# design.net
KiCad netlist of a schematic drawn in Altium Designer
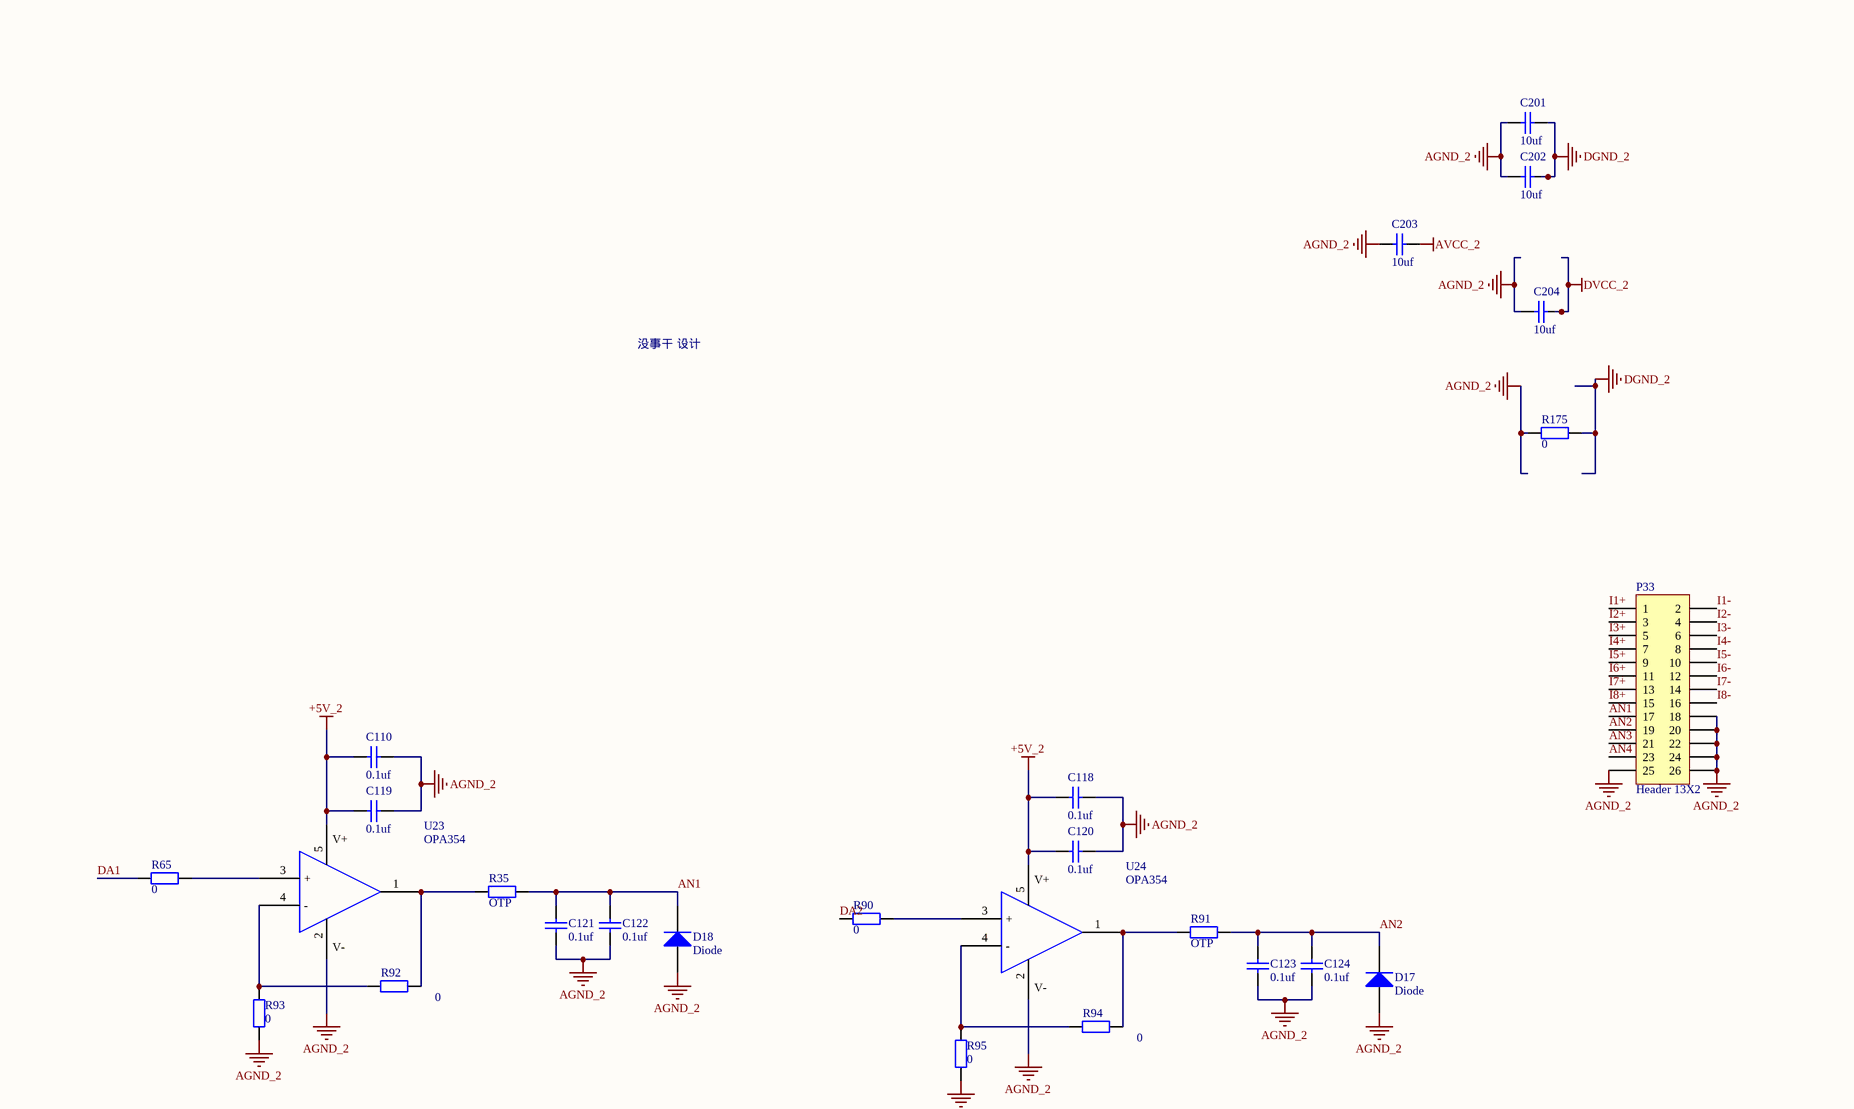
[diagram p0: 模拟量输入输出.SchDoc, top left]
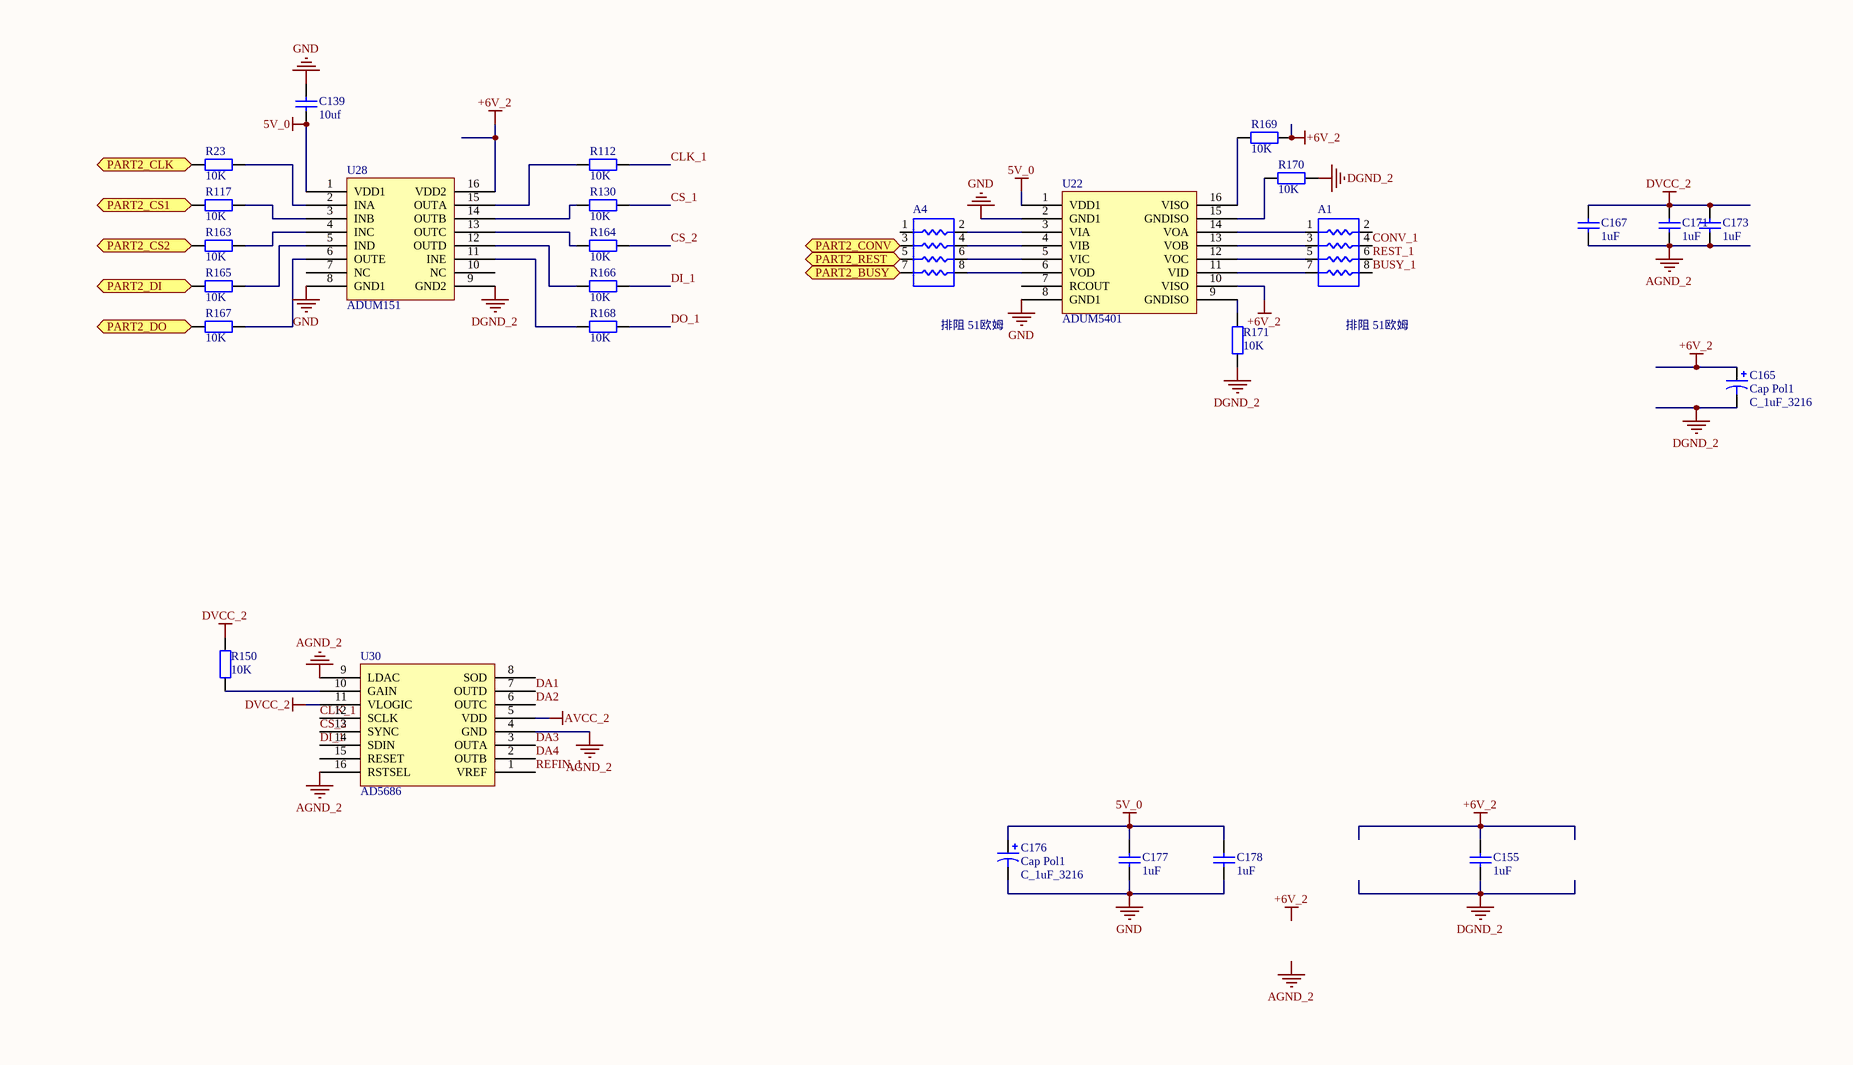
[diagram p1: 模拟量输入输出.SchDoc, top right]
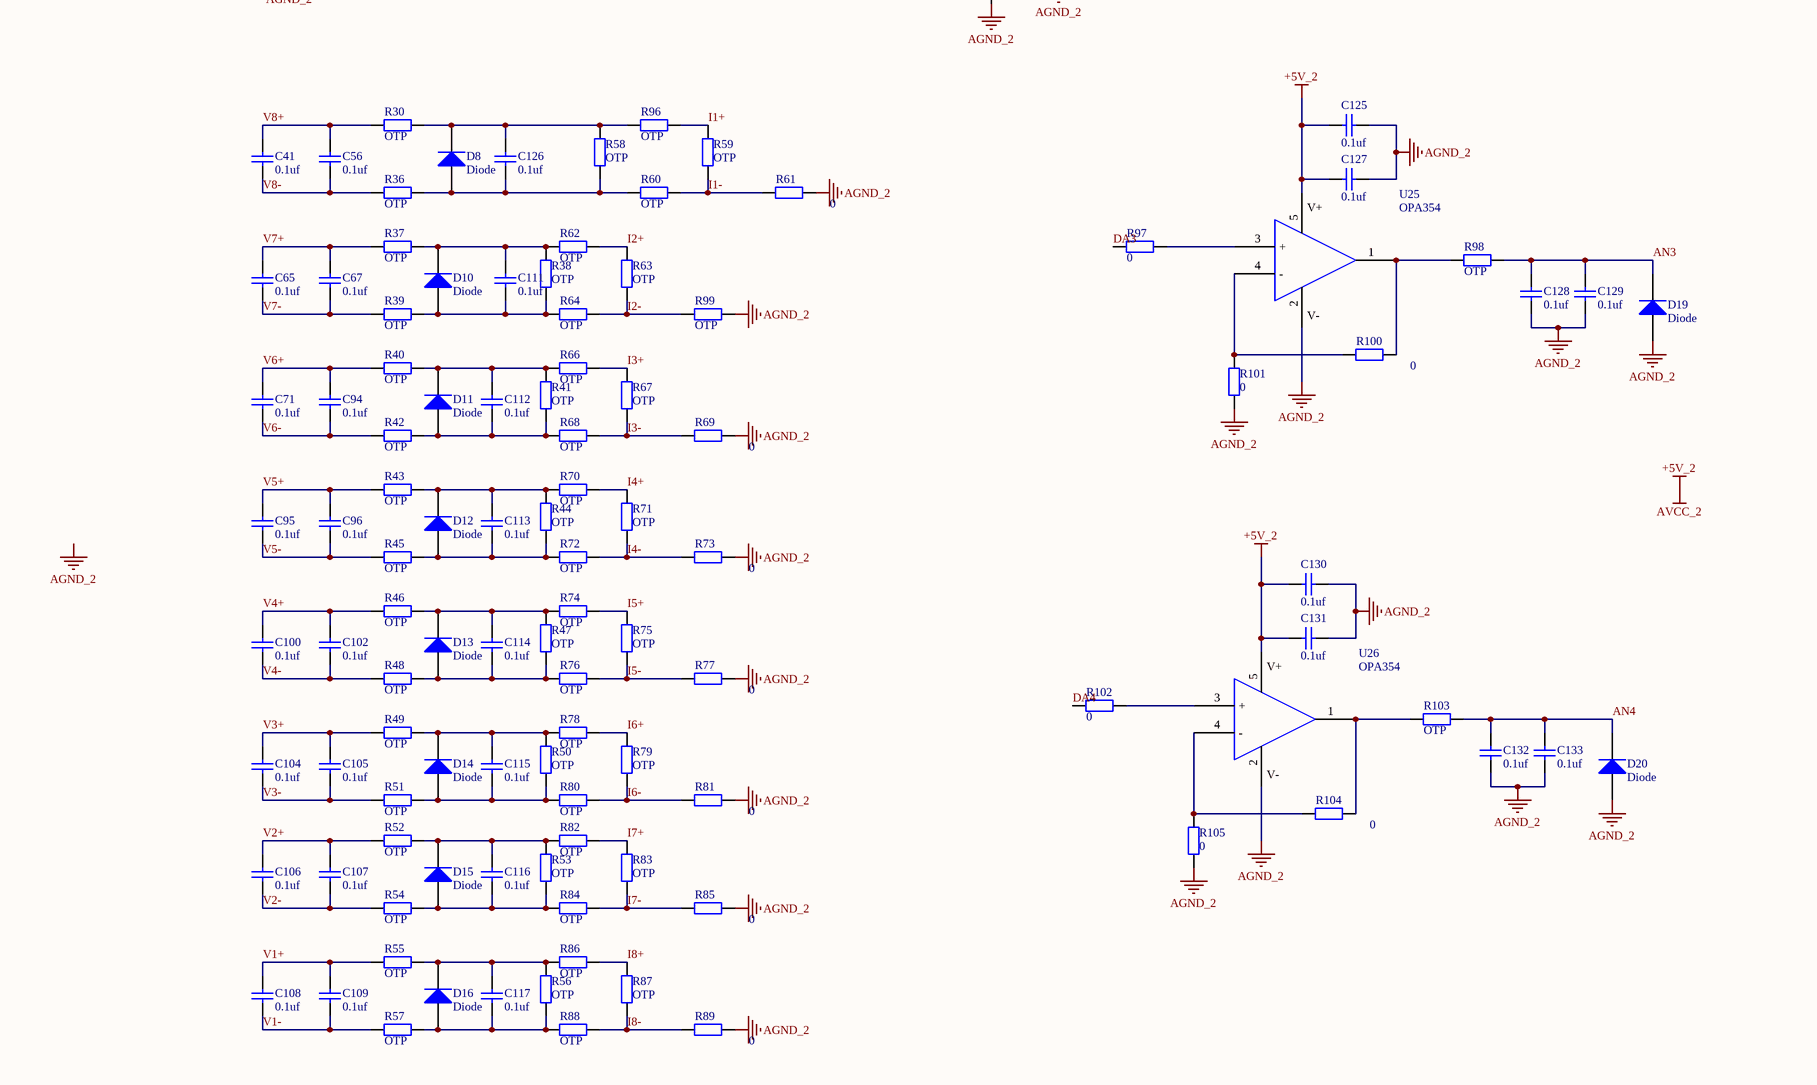
[diagram p2: 模拟量输入输出.SchDoc, bottom left]
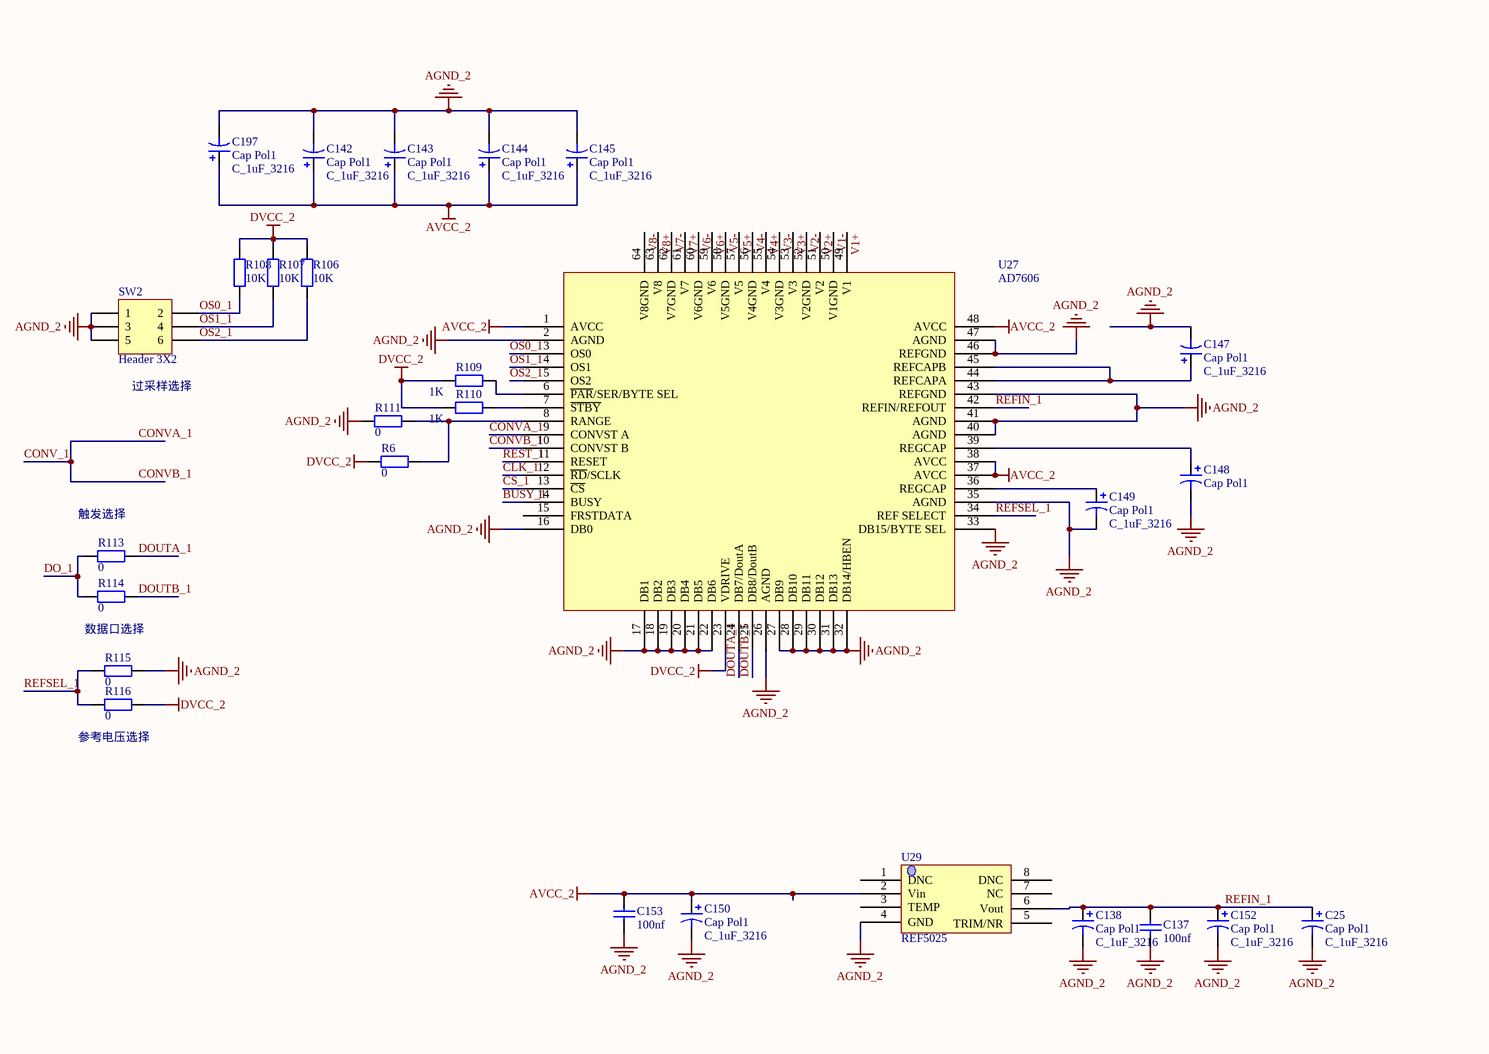
[diagram p3: 模拟量输入输出.SchDoc, bottom right]

(export (version "E")
  (design (tool "Eeschema 10.0.6"))
  (components
    (comp (ref "A1")
      (value "排阻 51欧姆")
      (footprint "RCA03-4D")
      (libsource (lib "AD7606V23A") (part "RESPACK5"))
    )
    (comp (ref "A4")
      (value "排阻 51欧姆")
      (footprint "RCA03-4D")
      (libsource (lib "AD7606V23A") (part "RESPACK5"))
    )
    (comp (ref "C25")
      (value "Cap Pol1")
      (footprint "3216")
      (description "Polarized Capacitor (Radial)")
      (fields (field (name "ALTIUM_VALUE") "C_1uF_3216") (field (name "PUBLISHER") "Altium Limited"))
      (libsource (lib "AD7606V23A") (part "Cap Pol1"))
    )
    (comp (ref "C41")
      (value "0.1uf")
      (footprint "0805C")
      (description "Capacitor")
      (fields (field (name "Comment") "Cap") (field (name "PUBLISHER") "Altium Limited"))
      (libsource (lib "Miscellaneous Devices") (part "Cap"))
    )
    (comp (ref "C56")
      (value "0.1uf")
      (footprint "0805C")
      (description "Capacitor")
      (fields (field (name "Comment") "Cap") (field (name "PUBLISHER") "Altium Limited"))
      (libsource (lib "Miscellaneous Devices") (part "Cap"))
    )
    (comp (ref "C65")
      (value "0.1uf")
      (footprint "0805C")
      (description "Capacitor")
      (fields (field (name "Comment") "Cap") (field (name "PUBLISHER") "Altium Limited"))
      (libsource (lib "Miscellaneous Devices") (part "Cap"))
    )
    (comp (ref "C67")
      (value "0.1uf")
      (footprint "0805C")
      (description "Capacitor")
      (fields (field (name "Comment") "Cap") (field (name "PUBLISHER") "Altium Limited"))
      (libsource (lib "Miscellaneous Devices") (part "Cap"))
    )
    (comp (ref "C71")
      (value "0.1uf")
      (footprint "0805C")
      (description "Capacitor")
      (fields (field (name "Comment") "Cap") (field (name "PUBLISHER") "Altium Limited"))
      (libsource (lib "Miscellaneous Devices") (part "Cap"))
    )
    (comp (ref "C94")
      (value "0.1uf")
      (footprint "0805C")
      (description "Capacitor")
      (fields (field (name "Comment") "Cap") (field (name "PUBLISHER") "Altium Limited"))
      (libsource (lib "Miscellaneous Devices") (part "Cap"))
    )
    (comp (ref "C95")
      (value "0.1uf")
      (footprint "0805C")
      (description "Capacitor")
      (fields (field (name "Comment") "Cap") (field (name "PUBLISHER") "Altium Limited"))
      (libsource (lib "Miscellaneous Devices") (part "Cap"))
    )
    (comp (ref "C96")
      (value "0.1uf")
      (footprint "0805C")
      (description "Capacitor")
      (fields (field (name "Comment") "Cap") (field (name "PUBLISHER") "Altium Limited"))
      (libsource (lib "Miscellaneous Devices") (part "Cap"))
    )
    (comp (ref "C100")
      (value "0.1uf")
      (footprint "0805C")
      (description "Capacitor")
      (fields (field (name "Comment") "Cap") (field (name "PUBLISHER") "Altium Limited"))
      (libsource (lib "Miscellaneous Devices") (part "Cap"))
    )
    (comp (ref "C102")
      (value "0.1uf")
      (footprint "0805C")
      (description "Capacitor")
      (fields (field (name "Comment") "Cap") (field (name "PUBLISHER") "Altium Limited"))
      (libsource (lib "Miscellaneous Devices") (part "Cap"))
    )
    (comp (ref "C104")
      (value "0.1uf")
      (footprint "0805C")
      (description "Capacitor")
      (fields (field (name "Comment") "Cap") (field (name "PUBLISHER") "Altium Limited"))
      (libsource (lib "Miscellaneous Devices") (part "Cap"))
    )
    (comp (ref "C105")
      (value "0.1uf")
      (footprint "0805C")
      (description "Capacitor")
      (fields (field (name "Comment") "Cap") (field (name "PUBLISHER") "Altium Limited"))
      (libsource (lib "Miscellaneous Devices") (part "Cap"))
    )
    (comp (ref "C106")
      (value "0.1uf")
      (footprint "0805C")
      (description "Capacitor")
      (fields (field (name "Comment") "Cap") (field (name "PUBLISHER") "Altium Limited"))
      (libsource (lib "Miscellaneous Devices") (part "Cap"))
    )
    (comp (ref "C107")
      (value "0.1uf")
      (footprint "0805C")
      (description "Capacitor")
      (fields (field (name "Comment") "Cap") (field (name "PUBLISHER") "Altium Limited"))
      (libsource (lib "Miscellaneous Devices") (part "Cap"))
    )
    (comp (ref "C108")
      (value "0.1uf")
      (footprint "0805C")
      (description "Capacitor")
      (fields (field (name "Comment") "Cap") (field (name "PUBLISHER") "Altium Limited"))
      (libsource (lib "Miscellaneous Devices") (part "Cap"))
    )
    (comp (ref "C109")
      (value "0.1uf")
      (footprint "0805C")
      (description "Capacitor")
      (fields (field (name "Comment") "Cap") (field (name "PUBLISHER") "Altium Limited"))
      (libsource (lib "Miscellaneous Devices") (part "Cap"))
    )
    (comp (ref "C110")
      (value "0.1uf")
      (footprint "0805C")
      (description "Capacitor")
      (fields (field (name "Comment") "Cap") (field (name "PUBLISHER") "Altium Limited"))
      (libsource (lib "Miscellaneous Devices") (part "Cap"))
    )
    (comp (ref "C111")
      (value "0.1uf")
      (footprint "0805C")
      (description "Capacitor")
      (fields (field (name "Comment") "Cap") (field (name "PUBLISHER") "Altium Limited"))
      (libsource (lib "Miscellaneous Devices") (part "Cap"))
    )
    (comp (ref "C112")
      (value "0.1uf")
      (footprint "0805C")
      (description "Capacitor")
      (fields (field (name "Comment") "Cap") (field (name "PUBLISHER") "Altium Limited"))
      (libsource (lib "Miscellaneous Devices") (part "Cap"))
    )
    (comp (ref "C113")
      (value "0.1uf")
      (footprint "0805C")
      (description "Capacitor")
      (fields (field (name "Comment") "Cap") (field (name "PUBLISHER") "Altium Limited"))
      (libsource (lib "Miscellaneous Devices") (part "Cap"))
    )
    (comp (ref "C114")
      (value "0.1uf")
      (footprint "0805C")
      (description "Capacitor")
      (fields (field (name "Comment") "Cap") (field (name "PUBLISHER") "Altium Limited"))
      (libsource (lib "Miscellaneous Devices") (part "Cap"))
    )
    (comp (ref "C115")
      (value "0.1uf")
      (footprint "0805C")
      (description "Capacitor")
      (fields (field (name "Comment") "Cap") (field (name "PUBLISHER") "Altium Limited"))
      (libsource (lib "Miscellaneous Devices") (part "Cap"))
    )
    (comp (ref "C116")
      (value "0.1uf")
      (footprint "0805C")
      (description "Capacitor")
      (fields (field (name "Comment") "Cap") (field (name "PUBLISHER") "Altium Limited"))
      (libsource (lib "Miscellaneous Devices") (part "Cap"))
    )
    (comp (ref "C117")
      (value "0.1uf")
      (footprint "0805C")
      (description "Capacitor")
      (fields (field (name "Comment") "Cap") (field (name "PUBLISHER") "Altium Limited"))
      (libsource (lib "Miscellaneous Devices") (part "Cap"))
    )
    (comp (ref "C118")
      (value "0.1uf")
      (footprint "0805C")
      (description "Capacitor")
      (fields (field (name "Comment") "Cap") (field (name "PUBLISHER") "Altium Limited"))
      (libsource (lib "Miscellaneous Devices") (part "Cap"))
    )
    (comp (ref "C119")
      (value "0.1uf")
      (footprint "0805C")
      (description "Capacitor")
      (fields (field (name "Comment") "Cap") (field (name "PUBLISHER") "Altium Limited"))
      (libsource (lib "Miscellaneous Devices") (part "Cap"))
    )
    (comp (ref "C120")
      (value "0.1uf")
      (footprint "0805C")
      (description "Capacitor")
      (fields (field (name "Comment") "Cap") (field (name "PUBLISHER") "Altium Limited"))
      (libsource (lib "Miscellaneous Devices") (part "Cap"))
    )
    (comp (ref "C121")
      (value "0.1uf")
      (footprint "0805C")
      (description "Capacitor")
      (fields (field (name "Comment") "Cap") (field (name "PUBLISHER") "Altium Limited"))
      (libsource (lib "Miscellaneous Devices") (part "Cap"))
    )
    (comp (ref "C122")
      (value "0.1uf")
      (footprint "0805C")
      (description "Capacitor")
      (fields (field (name "Comment") "Cap") (field (name "PUBLISHER") "Altium Limited"))
      (libsource (lib "Miscellaneous Devices") (part "Cap"))
    )
    (comp (ref "C123")
      (value "0.1uf")
      (footprint "0805C")
      (description "Capacitor")
      (fields (field (name "Comment") "Cap") (field (name "PUBLISHER") "Altium Limited"))
      (libsource (lib "Miscellaneous Devices") (part "Cap"))
    )
    (comp (ref "C124")
      (value "0.1uf")
      (footprint "0805C")
      (description "Capacitor")
      (fields (field (name "Comment") "Cap") (field (name "PUBLISHER") "Altium Limited"))
      (libsource (lib "Miscellaneous Devices") (part "Cap"))
    )
    (comp (ref "C125")
      (value "0.1uf")
      (footprint "0805C")
      (description "Capacitor")
      (fields (field (name "Comment") "Cap") (field (name "PUBLISHER") "Altium Limited"))
      (libsource (lib "Miscellaneous Devices") (part "Cap"))
    )
    (comp (ref "C126")
      (value "0.1uf")
      (footprint "0805C")
      (description "Capacitor")
      (fields (field (name "Comment") "Cap") (field (name "PUBLISHER") "Altium Limited"))
      (libsource (lib "Miscellaneous Devices") (part "Cap"))
    )
    (comp (ref "C127")
      (value "0.1uf")
      (footprint "0805C")
      (description "Capacitor")
      (fields (field (name "Comment") "Cap") (field (name "PUBLISHER") "Altium Limited"))
      (libsource (lib "Miscellaneous Devices") (part "Cap"))
    )
    (comp (ref "C128")
      (value "0.1uf")
      (footprint "0805C")
      (description "Capacitor")
      (fields (field (name "Comment") "Cap") (field (name "PUBLISHER") "Altium Limited"))
      (libsource (lib "Miscellaneous Devices") (part "Cap"))
    )
    (comp (ref "C129")
      (value "0.1uf")
      (footprint "0805C")
      (description "Capacitor")
      (fields (field (name "Comment") "Cap") (field (name "PUBLISHER") "Altium Limited"))
      (libsource (lib "Miscellaneous Devices") (part "Cap"))
    )
    (comp (ref "C130")
      (value "0.1uf")
      (footprint "0805C")
      (description "Capacitor")
      (fields (field (name "Comment") "Cap") (field (name "PUBLISHER") "Altium Limited"))
      (libsource (lib "Miscellaneous Devices") (part "Cap"))
    )
    (comp (ref "C131")
      (value "0.1uf")
      (footprint "0805C")
      (description "Capacitor")
      (fields (field (name "Comment") "Cap") (field (name "PUBLISHER") "Altium Limited"))
      (libsource (lib "Miscellaneous Devices") (part "Cap"))
    )
    (comp (ref "C132")
      (value "0.1uf")
      (footprint "0805C")
      (description "Capacitor")
      (fields (field (name "Comment") "Cap") (field (name "PUBLISHER") "Altium Limited"))
      (libsource (lib "Miscellaneous Devices") (part "Cap"))
    )
    (comp (ref "C133")
      (value "0.1uf")
      (footprint "0805C")
      (description "Capacitor")
      (fields (field (name "Comment") "Cap") (field (name "PUBLISHER") "Altium Limited"))
      (libsource (lib "Miscellaneous Devices") (part "Cap"))
    )
    (comp (ref "C137")
      (value "100nf")
      (footprint "0805C")
      (description "Capacitor")
      (fields (field (name "Comment") "Cap") (field (name "PUBLISHER") "Altium Limited"))
      (libsource (lib "Miscellaneous Devices") (part "Cap"))
    )
    (comp (ref "C138")
      (value "Cap Pol1")
      (footprint "3216")
      (description "Polarized Capacitor (Radial)")
      (fields (field (name "ALTIUM_VALUE") "C_1uF_3216") (field (name "PUBLISHER") "Altium Limited"))
      (libsource (lib "AD7606V23A") (part "Cap Pol1"))
    )
    (comp (ref "C139")
      (value "10uf")
      (footprint "0805C")
      (description "Capacitor")
      (fields (field (name "Comment") "Cap") (field (name "PUBLISHER") "Altium Limited"))
      (libsource (lib "Miscellaneous Devices") (part "Cap"))
    )
    (comp (ref "C142")
      (value "Cap Pol1")
      (footprint "3216")
      (description "Polarized Capacitor (Radial)")
      (fields (field (name "ALTIUM_VALUE") "C_1uF_3216") (field (name "PUBLISHER") "Altium Limited"))
      (libsource (lib "AD7606V23A") (part "Cap Pol1"))
    )
    (comp (ref "C143")
      (value "Cap Pol1")
      (footprint "3216")
      (description "Polarized Capacitor (Radial)")
      (fields (field (name "ALTIUM_VALUE") "C_1uF_3216") (field (name "PUBLISHER") "Altium Limited"))
      (libsource (lib "AD7606V23A") (part "Cap Pol1"))
    )
    (comp (ref "C144")
      (value "Cap Pol1")
      (footprint "3216")
      (description "Polarized Capacitor (Radial)")
      (fields (field (name "ALTIUM_VALUE") "C_1uF_3216") (field (name "PUBLISHER") "Altium Limited"))
      (libsource (lib "AD7606V23A") (part "Cap Pol1"))
    )
    (comp (ref "C145")
      (value "Cap Pol1")
      (footprint "3216")
      (description "Polarized Capacitor (Radial)")
      (fields (field (name "ALTIUM_VALUE") "C_1uF_3216") (field (name "PUBLISHER") "Altium Limited"))
      (libsource (lib "AD7606V23A") (part "Cap Pol1"))
    )
    (comp (ref "C147")
      (value "Cap Pol1")
      (footprint "3216")
      (description "Polarized Capacitor (Radial)")
      (fields (field (name "ALTIUM_VALUE") "C_1uF_3216") (field (name "PUBLISHER") "Altium Limited"))
      (libsource (lib "AD7606V23A") (part "Cap Pol1"))
    )
    (comp (ref "C148")
      (value "Cap Pol1")
      (footprint "3216")
      (description "Polarized Capacitor (Radial)")
      (fields (field (name "PUBLISHER") "Altium Limited"))
      (libsource (lib "AD7606V23A") (part "Cap Pol1"))
    )
    (comp (ref "C149")
      (value "Cap Pol1")
      (footprint "3216")
      (description "Polarized Capacitor (Radial)")
      (fields (field (name "ALTIUM_VALUE") "C_1uF_3216") (field (name "PUBLISHER") "Altium Limited"))
      (libsource (lib "AD7606V23A") (part "Cap Pol1"))
    )
    (comp (ref "C150")
      (value "Cap Pol1")
      (footprint "3216")
      (description "Polarized Capacitor (Radial)")
      (fields (field (name "ALTIUM_VALUE") "C_1uF_3216") (field (name "PUBLISHER") "Altium Limited"))
      (libsource (lib "AD7606V23A") (part "Cap Pol1"))
    )
    (comp (ref "C152")
      (value "Cap Pol1")
      (footprint "3216")
      (description "Polarized Capacitor (Radial)")
      (fields (field (name "ALTIUM_VALUE") "C_1uF_3216") (field (name "PUBLISHER") "Altium Limited"))
      (libsource (lib "AD7606V23A") (part "Cap Pol1"))
    )
    (comp (ref "C153")
      (value "100nf")
      (footprint "0805C")
      (description "Capacitor")
      (fields (field (name "Comment") "Cap") (field (name "PUBLISHER") "Altium Limited"))
      (libsource (lib "Miscellaneous Devices") (part "Cap"))
    )
    (comp (ref "C155")
      (value "1uF")
      (footprint "0805C")
      (description "Capacitor")
      (fields (field (name "PUBLISHER") "Altium Limited"))
      (libsource (lib "Miscellaneous Devices") (part "Cap"))
    )
    (comp (ref "C165")
      (value "Cap Pol1")
      (footprint "3216")
      (description "Polarized Capacitor (Radial)")
      (fields (field (name "ALTIUM_VALUE") "C_1uF_3216") (field (name "PUBLISHER") "Altium Limited"))
      (libsource (lib "AD7606V23A") (part "Cap Pol1"))
    )
    (comp (ref "C167")
      (value "1uF")
      (footprint "0805C")
      (description "Capacitor")
      (fields (field (name "PUBLISHER") "Altium Limited"))
      (libsource (lib "Miscellaneous Devices") (part "Cap"))
    )
    (comp (ref "C171")
      (value "1uF")
      (footprint "0805C")
      (description "Capacitor")
      (fields (field (name "PUBLISHER") "Altium Limited"))
      (libsource (lib "Miscellaneous Devices") (part "Cap"))
    )
    (comp (ref "C173")
      (value "1uF")
      (footprint "0805C")
      (description "Capacitor")
      (fields (field (name "PUBLISHER") "Altium Limited"))
      (libsource (lib "Miscellaneous Devices") (part "Cap"))
    )
    (comp (ref "C176")
      (value "Cap Pol1")
      (footprint "3216")
      (description "Polarized Capacitor (Radial)")
      (fields (field (name "ALTIUM_VALUE") "C_1uF_3216") (field (name "PUBLISHER") "Altium Limited"))
      (libsource (lib "AD7606V23A") (part "Cap Pol1"))
    )
    (comp (ref "C177")
      (value "1uF")
      (footprint "0805C")
      (description "Capacitor")
      (fields (field (name "PUBLISHER") "Altium Limited"))
      (libsource (lib "Miscellaneous Devices") (part "Cap"))
    )
    (comp (ref "C178")
      (value "1uF")
      (footprint "0805C")
      (description "Capacitor")
      (fields (field (name "PUBLISHER") "Altium Limited"))
      (libsource (lib "Miscellaneous Devices") (part "Cap"))
    )
    (comp (ref "C197")
      (value "Cap Pol1")
      (footprint "3216")
      (description "Polarized Capacitor (Radial)")
      (fields (field (name "ALTIUM_VALUE") "C_1uF_3216") (field (name "PUBLISHER") "Altium Limited"))
      (libsource (lib "AD7606V23A") (part "Cap Pol1"))
    )
    (comp (ref "C201")
      (value "10uf")
      (footprint "0805C")
      (description "Capacitor")
      (fields (field (name "Comment") "Cap") (field (name "PUBLISHER") "Altium Limited"))
      (libsource (lib "Miscellaneous Devices") (part "Cap"))
    )
    (comp (ref "C202")
      (value "10uf")
      (footprint "0805C")
      (description "Capacitor")
      (fields (field (name "Comment") "Cap") (field (name "PUBLISHER") "Altium Limited"))
      (libsource (lib "Miscellaneous Devices") (part "Cap"))
    )
    (comp (ref "C203")
      (value "10uf")
      (footprint "0805C")
      (description "Capacitor")
      (fields (field (name "Comment") "Cap") (field (name "PUBLISHER") "Altium Limited"))
      (libsource (lib "Miscellaneous Devices") (part "Cap"))
    )
    (comp (ref "C204")
      (value "10uf")
      (footprint "0805C")
      (description "Capacitor")
      (fields (field (name "Comment") "Cap") (field (name "PUBLISHER") "Altium Limited"))
      (libsource (lib "Miscellaneous Devices") (part "Cap"))
    )
    (comp (ref "D8")
      (value "Diode")
      (footprint "SMA")
      (description "Default Diode")
      (fields (field (name "PUBLISHER") "Altium Limited"))
      (libsource (lib "Miscellaneous Devices") (part "Diode"))
    )
    (comp (ref "D10")
      (value "Diode")
      (footprint "SMA")
      (description "Default Diode")
      (fields (field (name "PUBLISHER") "Altium Limited"))
      (libsource (lib "Miscellaneous Devices") (part "Diode"))
    )
    (comp (ref "D11")
      (value "Diode")
      (footprint "SMA")
      (description "Default Diode")
      (fields (field (name "PUBLISHER") "Altium Limited"))
      (libsource (lib "Miscellaneous Devices") (part "Diode"))
    )
    (comp (ref "D12")
      (value "Diode")
      (footprint "SMA")
      (description "Default Diode")
      (fields (field (name "PUBLISHER") "Altium Limited"))
      (libsource (lib "Miscellaneous Devices") (part "Diode"))
    )
    (comp (ref "D13")
      (value "Diode")
      (footprint "SMA")
      (description "Default Diode")
      (fields (field (name "PUBLISHER") "Altium Limited"))
      (libsource (lib "Miscellaneous Devices") (part "Diode"))
    )
    (comp (ref "D14")
      (value "Diode")
      (footprint "SMA")
      (description "Default Diode")
      (fields (field (name "PUBLISHER") "Altium Limited"))
      (libsource (lib "Miscellaneous Devices") (part "Diode"))
    )
    (comp (ref "D15")
      (value "Diode")
      (footprint "SMA")
      (description "Default Diode")
      (fields (field (name "PUBLISHER") "Altium Limited"))
      (libsource (lib "Miscellaneous Devices") (part "Diode"))
    )
    (comp (ref "D16")
      (value "Diode")
      (footprint "SMA")
      (description "Default Diode")
      (fields (field (name "PUBLISHER") "Altium Limited"))
      (libsource (lib "Miscellaneous Devices") (part "Diode"))
    )
    (comp (ref "D17")
      (value "Diode")
      (footprint "SMA")
      (description "Default Diode")
      (fields (field (name "PUBLISHER") "Altium Limited"))
      (libsource (lib "Miscellaneous Devices") (part "Diode"))
    )
    (comp (ref "D18")
      (value "Diode")
      (footprint "SMA")
      (description "Default Diode")
      (fields (field (name "PUBLISHER") "Altium Limited"))
      (libsource (lib "Miscellaneous Devices") (part "Diode"))
    )
    (comp (ref "D19")
      (value "Diode")
      (footprint "SMA")
      (description "Default Diode")
      (fields (field (name "PUBLISHER") "Altium Limited"))
      (libsource (lib "Miscellaneous Devices") (part "Diode"))
    )
    (comp (ref "D20")
      (value "Diode")
      (footprint "SMA")
      (description "Default Diode")
      (fields (field (name "PUBLISHER") "Altium Limited"))
      (libsource (lib "Miscellaneous Devices") (part "Diode"))
    )
    (comp (ref "P33")
      (value "Header 13X2")
      (footprint "3.5MM-2*12P")
      (description "Header, 13-Pin, Dual row")
      (fields (field (name "PUBLISHER") "Altium Limited"))
      (libsource (lib "Miscellaneous Connectors") (part "Header 13X2"))
    )
    (comp (ref "R6")
      (value "0")
      (footprint "0805R")
      (description "Resistor")
      (fields (field (name "Comment") "Res2") (field (name "PUBLISHER") "Altium Limited"))
      (libsource (lib "") (part "Res2_1"))
    )
    (comp (ref "R23")
      (value "10K")
      (footprint "0805R")
      (description "Resistor")
      (fields (field (name "Comment") "Res2") (field (name "PUBLISHER") "Altium Limited"))
      (libsource (lib "Miscellaneous Devices") (part "Res2"))
    )
    (comp (ref "R30")
      (value "OTP")
      (footprint "0805R")
      (description "Resistor")
      (fields (field (name "Comment") "Res2") (field (name "PUBLISHER") "Altium Limited"))
      (libsource (lib "") (part "Res2_1"))
    )
    (comp (ref "R35")
      (value "OTP")
      (footprint "0805R")
      (description "Resistor")
      (fields (field (name "Comment") "Res2") (field (name "PUBLISHER") "Altium Limited"))
      (libsource (lib "") (part "Res2_2"))
    )
    (comp (ref "R36")
      (value "OTP")
      (footprint "0805R")
      (description "Resistor")
      (fields (field (name "Comment") "Res2") (field (name "PUBLISHER") "Altium Limited"))
      (libsource (lib "") (part "Res2_1"))
    )
    (comp (ref "R37")
      (value "OTP")
      (footprint "0805R")
      (description "Resistor")
      (fields (field (name "Comment") "Res2") (field (name "PUBLISHER") "Altium Limited"))
      (libsource (lib "") (part "Res2_1"))
    )
    (comp (ref "R38")
      (value "OTP")
      (footprint "0805R")
      (description "Resistor")
      (fields (field (name "Comment") "Res2") (field (name "PUBLISHER") "Altium Limited"))
      (libsource (lib "Miscellaneous Devices") (part "Res2"))
    )
    (comp (ref "R39")
      (value "OTP")
      (footprint "0805R")
      (description "Resistor")
      (fields (field (name "Comment") "Res2") (field (name "PUBLISHER") "Altium Limited"))
      (libsource (lib "") (part "Res2_1"))
    )
    (comp (ref "R40")
      (value "OTP")
      (footprint "0805R")
      (description "Resistor")
      (fields (field (name "Comment") "Res2") (field (name "PUBLISHER") "Altium Limited"))
      (libsource (lib "") (part "Res2_1"))
    )
    (comp (ref "R41")
      (value "OTP")
      (footprint "0805R")
      (description "Resistor")
      (fields (field (name "Comment") "Res2") (field (name "PUBLISHER") "Altium Limited"))
      (libsource (lib "Miscellaneous Devices") (part "Res2"))
    )
    (comp (ref "R42")
      (value "OTP")
      (footprint "0805R")
      (description "Resistor")
      (fields (field (name "Comment") "Res2") (field (name "PUBLISHER") "Altium Limited"))
      (libsource (lib "") (part "Res2_1"))
    )
    (comp (ref "R43")
      (value "OTP")
      (footprint "0805R")
      (description "Resistor")
      (fields (field (name "Comment") "Res2") (field (name "PUBLISHER") "Altium Limited"))
      (libsource (lib "") (part "Res2_1"))
    )
    (comp (ref "R44")
      (value "OTP")
      (footprint "0805R")
      (description "Resistor")
      (fields (field (name "Comment") "Res2") (field (name "PUBLISHER") "Altium Limited"))
      (libsource (lib "Miscellaneous Devices") (part "Res2"))
    )
    (comp (ref "R45")
      (value "OTP")
      (footprint "0805R")
      (description "Resistor")
      (fields (field (name "Comment") "Res2") (field (name "PUBLISHER") "Altium Limited"))
      (libsource (lib "") (part "Res2_1"))
    )
    (comp (ref "R46")
      (value "OTP")
      (footprint "0805R")
      (description "Resistor")
      (fields (field (name "Comment") "Res2") (field (name "PUBLISHER") "Altium Limited"))
      (libsource (lib "") (part "Res2_1"))
    )
    (comp (ref "R47")
      (value "OTP")
      (footprint "0805R")
      (description "Resistor")
      (fields (field (name "Comment") "Res2") (field (name "PUBLISHER") "Altium Limited"))
      (libsource (lib "Miscellaneous Devices") (part "Res2"))
    )
    (comp (ref "R48")
      (value "OTP")
      (footprint "0805R")
      (description "Resistor")
      (fields (field (name "Comment") "Res2") (field (name "PUBLISHER") "Altium Limited"))
      (libsource (lib "") (part "Res2_1"))
    )
    (comp (ref "R49")
      (value "OTP")
      (footprint "0805R")
      (description "Resistor")
      (fields (field (name "Comment") "Res2") (field (name "PUBLISHER") "Altium Limited"))
      (libsource (lib "") (part "Res2_1"))
    )
    (comp (ref "R50")
      (value "OTP")
      (footprint "0805R")
      (description "Resistor")
      (fields (field (name "Comment") "Res2") (field (name "PUBLISHER") "Altium Limited"))
      (libsource (lib "Miscellaneous Devices") (part "Res2"))
    )
    (comp (ref "R51")
      (value "OTP")
      (footprint "0805R")
      (description "Resistor")
      (fields (field (name "Comment") "Res2") (field (name "PUBLISHER") "Altium Limited"))
      (libsource (lib "") (part "Res2_1"))
    )
    (comp (ref "R52")
      (value "OTP")
      (footprint "0805R")
      (description "Resistor")
      (fields (field (name "Comment") "Res2") (field (name "PUBLISHER") "Altium Limited"))
      (libsource (lib "") (part "Res2_1"))
    )
    (comp (ref "R53")
      (value "OTP")
      (footprint "0805R")
      (description "Resistor")
      (fields (field (name "Comment") "Res2") (field (name "PUBLISHER") "Altium Limited"))
      (libsource (lib "Miscellaneous Devices") (part "Res2"))
    )
    (comp (ref "R54")
      (value "OTP")
      (footprint "0805R")
      (description "Resistor")
      (fields (field (name "Comment") "Res2") (field (name "PUBLISHER") "Altium Limited"))
      (libsource (lib "") (part "Res2_1"))
    )
    (comp (ref "R55")
      (value "OTP")
      (footprint "0805R")
      (description "Resistor")
      (fields (field (name "Comment") "Res2") (field (name "PUBLISHER") "Altium Limited"))
      (libsource (lib "") (part "Res2_1"))
    )
    (comp (ref "R56")
      (value "OTP")
      (footprint "0805R")
      (description "Resistor")
      (fields (field (name "Comment") "Res2") (field (name "PUBLISHER") "Altium Limited"))
      (libsource (lib "Miscellaneous Devices") (part "Res2"))
    )
    (comp (ref "R57")
      (value "OTP")
      (footprint "0805R")
      (description "Resistor")
      (fields (field (name "Comment") "Res2") (field (name "PUBLISHER") "Altium Limited"))
      (libsource (lib "") (part "Res2_1"))
    )
    (comp (ref "R58")
      (value "OTP")
      (footprint "0805R")
      (description "Resistor")
      (fields (field (name "Comment") "Res2") (field (name "PUBLISHER") "Altium Limited"))
      (libsource (lib "") (part "Res2_3"))
    )
    (comp (ref "R59")
      (value "OTP")
      (footprint "FB1206")
      (description "Resistor")
      (fields (field (name "Comment") "Res2") (field (name "PUBLISHER") "Altium Limited"))
      (libsource (lib "") (part "Res2_3"))
    )
    (comp (ref "R60")
      (value "OTP")
      (footprint "0805R")
      (description "Resistor")
      (fields (field (name "Comment") "Res2") (field (name "PUBLISHER") "Altium Limited"))
      (libsource (lib "") (part "Res2_2"))
    )
    (comp (ref "R61")
      (value "0")
      (footprint "0603AR")
      (description "Resistor")
      (fields (field (name "Comment") "Res2") (field (name "PUBLISHER") "Altium Limited"))
      (libsource (lib "") (part "Res2_1"))
    )
    (comp (ref "R62")
      (value "OTP")
      (footprint "0805R")
      (description "Resistor")
      (fields (field (name "Comment") "Res2") (field (name "PUBLISHER") "Altium Limited"))
      (libsource (lib "") (part "Res2_2"))
    )
    (comp (ref "R63")
      (value "OTP")
      (footprint "FB1206")
      (description "Resistor")
      (fields (field (name "Comment") "Res2") (field (name "PUBLISHER") "Altium Limited"))
      (libsource (lib "Miscellaneous Devices") (part "Res2"))
    )
    (comp (ref "R64")
      (value "OTP")
      (footprint "0805R")
      (description "Resistor")
      (fields (field (name "Comment") "Res2") (field (name "PUBLISHER") "Altium Limited"))
      (libsource (lib "") (part "Res2_2"))
    )
    (comp (ref "R65")
      (value "0")
      (footprint "0805R")
      (description "Resistor")
      (fields (field (name "Comment") "Res2") (field (name "PUBLISHER") "Altium Limited"))
      (libsource (lib "") (part "Res2_2"))
    )
    (comp (ref "R66")
      (value "OTP")
      (footprint "0805R")
      (description "Resistor")
      (fields (field (name "Comment") "Res2") (field (name "PUBLISHER") "Altium Limited"))
      (libsource (lib "") (part "Res2_2"))
    )
    (comp (ref "R67")
      (value "OTP")
      (footprint "FB1206")
      (description "Resistor")
      (fields (field (name "Comment") "Res2") (field (name "PUBLISHER") "Altium Limited"))
      (libsource (lib "Miscellaneous Devices") (part "Res2"))
    )
    (comp (ref "R68")
      (value "OTP")
      (footprint "0805R")
      (description "Resistor")
      (fields (field (name "Comment") "Res2") (field (name "PUBLISHER") "Altium Limited"))
      (libsource (lib "") (part "Res2_2"))
    )
    (comp (ref "R69")
      (value "0")
      (footprint "0603AR")
      (description "Resistor")
      (fields (field (name "Comment") "Res2") (field (name "PUBLISHER") "Altium Limited"))
      (libsource (lib "") (part "Res2_1"))
    )
    (comp (ref "R70")
      (value "OTP")
      (footprint "0805R")
      (description "Resistor")
      (fields (field (name "Comment") "Res2") (field (name "PUBLISHER") "Altium Limited"))
      (libsource (lib "") (part "Res2_2"))
    )
    (comp (ref "R71")
      (value "OTP")
      (footprint "FB1206")
      (description "Resistor")
      (fields (field (name "Comment") "Res2") (field (name "PUBLISHER") "Altium Limited"))
      (libsource (lib "Miscellaneous Devices") (part "Res2"))
    )
    (comp (ref "R72")
      (value "OTP")
      (footprint "0805R")
      (description "Resistor")
      (fields (field (name "Comment") "Res2") (field (name "PUBLISHER") "Altium Limited"))
      (libsource (lib "") (part "Res2_2"))
    )
    (comp (ref "R73")
      (value "0")
      (footprint "0603AR")
      (description "Resistor")
      (fields (field (name "Comment") "Res2") (field (name "PUBLISHER") "Altium Limited"))
      (libsource (lib "") (part "Res2_1"))
    )
    (comp (ref "R74")
      (value "OTP")
      (footprint "0805R")
      (description "Resistor")
      (fields (field (name "Comment") "Res2") (field (name "PUBLISHER") "Altium Limited"))
      (libsource (lib "") (part "Res2_2"))
    )
    (comp (ref "R75")
      (value "OTP")
      (footprint "FB1206")
      (description "Resistor")
      (fields (field (name "Comment") "Res2") (field (name "PUBLISHER") "Altium Limited"))
      (libsource (lib "Miscellaneous Devices") (part "Res2"))
    )
    (comp (ref "R76")
      (value "OTP")
      (footprint "0805R")
      (description "Resistor")
      (fields (field (name "Comment") "Res2") (field (name "PUBLISHER") "Altium Limited"))
      (libsource (lib "") (part "Res2_2"))
    )
    (comp (ref "R77")
      (value "0")
      (footprint "0603AR")
      (description "Resistor")
      (fields (field (name "Comment") "Res2") (field (name "PUBLISHER") "Altium Limited"))
      (libsource (lib "") (part "Res2_1"))
    )
    (comp (ref "R78")
      (value "OTP")
      (footprint "0805R")
      (description "Resistor")
      (fields (field (name "Comment") "Res2") (field (name "PUBLISHER") "Altium Limited"))
      (libsource (lib "") (part "Res2_2"))
    )
    (comp (ref "R79")
      (value "OTP")
      (footprint "FB1206")
      (description "Resistor")
      (fields (field (name "Comment") "Res2") (field (name "PUBLISHER") "Altium Limited"))
      (libsource (lib "Miscellaneous Devices") (part "Res2"))
    )
    (comp (ref "R80")
      (value "OTP")
      (footprint "0805R")
      (description "Resistor")
      (fields (field (name "Comment") "Res2") (field (name "PUBLISHER") "Altium Limited"))
      (libsource (lib "") (part "Res2_2"))
    )
    (comp (ref "R81")
      (value "0")
      (footprint "0603AR")
      (description "Resistor")
      (fields (field (name "Comment") "Res2") (field (name "PUBLISHER") "Altium Limited"))
      (libsource (lib "") (part "Res2_1"))
    )
    (comp (ref "R82")
      (value "OTP")
      (footprint "0805R")
      (description "Resistor")
      (fields (field (name "Comment") "Res2") (field (name "PUBLISHER") "Altium Limited"))
      (libsource (lib "") (part "Res2_2"))
    )
    (comp (ref "R83")
      (value "OTP")
      (footprint "FB1206")
      (description "Resistor")
      (fields (field (name "Comment") "Res2") (field (name "PUBLISHER") "Altium Limited"))
      (libsource (lib "Miscellaneous Devices") (part "Res2"))
    )
    (comp (ref "R84")
      (value "OTP")
      (footprint "0805R")
      (description "Resistor")
      (fields (field (name "Comment") "Res2") (field (name "PUBLISHER") "Altium Limited"))
      (libsource (lib "") (part "Res2_2"))
    )
    (comp (ref "R85")
      (value "0")
      (footprint "0603AR")
      (description "Resistor")
      (fields (field (name "Comment") "Res2") (field (name "PUBLISHER") "Altium Limited"))
      (libsource (lib "") (part "Res2_1"))
    )
    (comp (ref "R86")
      (value "OTP")
      (footprint "0805R")
      (description "Resistor")
      (fields (field (name "Comment") "Res2") (field (name "PUBLISHER") "Altium Limited"))
      (libsource (lib "") (part "Res2_2"))
    )
    (comp (ref "R87")
      (value "OTP")
      (footprint "FB1206")
      (description "Resistor")
      (fields (field (name "Comment") "Res2") (field (name "PUBLISHER") "Altium Limited"))
      (libsource (lib "Miscellaneous Devices") (part "Res2"))
    )
    (comp (ref "R88")
      (value "OTP")
      (footprint "0805R")
      (description "Resistor")
      (fields (field (name "Comment") "Res2") (field (name "PUBLISHER") "Altium Limited"))
      (libsource (lib "") (part "Res2_2"))
    )
    (comp (ref "R89")
      (value "0")
      (footprint "0603AR")
      (description "Resistor")
      (fields (field (name "Comment") "Res2") (field (name "PUBLISHER") "Altium Limited"))
      (libsource (lib "") (part "Res2_1"))
    )
    (comp (ref "R90")
      (value "0")
      (footprint "0805R")
      (description "Resistor")
      (fields (field (name "Comment") "Res2") (field (name "PUBLISHER") "Altium Limited"))
      (libsource (lib "") (part "Res2_2"))
    )
    (comp (ref "R91")
      (value "OTP")
      (footprint "0805R")
      (description "Resistor")
      (fields (field (name "Comment") "Res2") (field (name "PUBLISHER") "Altium Limited"))
      (libsource (lib "") (part "Res2_2"))
    )
    (comp (ref "R92")
      (value "0")
      (footprint "0805R")
      (description "Resistor")
      (fields (field (name "Comment") "Res2") (field (name "PUBLISHER") "Altium Limited"))
      (libsource (lib "") (part "Res2_1"))
    )
    (comp (ref "R93")
      (value "0")
      (footprint "0805R")
      (description "Resistor")
      (fields (field (name "Comment") "Res2") (field (name "PUBLISHER") "Altium Limited"))
      (libsource (lib "Miscellaneous Devices") (part "Res2"))
    )
    (comp (ref "R94")
      (value "0")
      (footprint "0805R")
      (description "Resistor")
      (fields (field (name "Comment") "Res2") (field (name "PUBLISHER") "Altium Limited"))
      (libsource (lib "") (part "Res2_1"))
    )
    (comp (ref "R95")
      (value "0")
      (footprint "0805R")
      (description "Resistor")
      (fields (field (name "Comment") "Res2") (field (name "PUBLISHER") "Altium Limited"))
      (libsource (lib "Miscellaneous Devices") (part "Res2"))
    )
    (comp (ref "R96")
      (value "OTP")
      (footprint "0805R")
      (description "Resistor")
      (fields (field (name "Comment") "Res2") (field (name "PUBLISHER") "Altium Limited"))
      (libsource (lib "") (part "Res2_2"))
    )
    (comp (ref "R97")
      (value "0")
      (footprint "0805R")
      (description "Resistor")
      (fields (field (name "Comment") "Res2") (field (name "PUBLISHER") "Altium Limited"))
      (libsource (lib "") (part "Res2_2"))
    )
    (comp (ref "R98")
      (value "OTP")
      (footprint "0805R")
      (description "Resistor")
      (fields (field (name "Comment") "Res2") (field (name "PUBLISHER") "Altium Limited"))
      (libsource (lib "") (part "Res2_2"))
    )
    (comp (ref "R99")
      (value "OTP")
      (footprint "0603AR")
      (description "Resistor")
      (fields (field (name "Comment") "Res2") (field (name "PUBLISHER") "Altium Limited"))
      (libsource (lib "") (part "Res2_1"))
    )
    (comp (ref "R100")
      (value "0")
      (footprint "0805R")
      (description "Resistor")
      (fields (field (name "Comment") "Res2") (field (name "PUBLISHER") "Altium Limited"))
      (libsource (lib "") (part "Res2_1"))
    )
    (comp (ref "R101")
      (value "0")
      (footprint "0805R")
      (description "Resistor")
      (fields (field (name "Comment") "Res2") (field (name "PUBLISHER") "Altium Limited"))
      (libsource (lib "Miscellaneous Devices") (part "Res2"))
    )
    (comp (ref "R102")
      (value "0")
      (footprint "0805R")
      (description "Resistor")
      (fields (field (name "Comment") "Res2") (field (name "PUBLISHER") "Altium Limited"))
      (libsource (lib "") (part "Res2_2"))
    )
    (comp (ref "R103")
      (value "OTP")
      (footprint "0805R")
      (description "Resistor")
      (fields (field (name "Comment") "Res2") (field (name "PUBLISHER") "Altium Limited"))
      (libsource (lib "") (part "Res2_2"))
    )
    (comp (ref "R104")
      (value "0")
      (footprint "0805R")
      (description "Resistor")
      (fields (field (name "Comment") "Res2") (field (name "PUBLISHER") "Altium Limited"))
      (libsource (lib "") (part "Res2_1"))
    )
    (comp (ref "R105")
      (value "0")
      (footprint "0805R")
      (description "Resistor")
      (fields (field (name "Comment") "Res2") (field (name "PUBLISHER") "Altium Limited"))
      (libsource (lib "Miscellaneous Devices") (part "Res2"))
    )
    (comp (ref "R106")
      (value "10K")
      (footprint "0805R")
      (description "Resistor")
      (fields (field (name "Comment") "Res2") (field (name "PUBLISHER") "Altium Limited"))
      (libsource (lib "Miscellaneous Devices") (part "Res2"))
    )
    (comp (ref "R107")
      (value "10K")
      (footprint "0805R")
      (description "Resistor")
      (fields (field (name "Comment") "Res2") (field (name "PUBLISHER") "Altium Limited"))
      (libsource (lib "Miscellaneous Devices") (part "Res2"))
    )
    (comp (ref "R108")
      (value "10K")
      (footprint "0805R")
      (description "Resistor")
      (fields (field (name "Comment") "Res2") (field (name "PUBLISHER") "Altium Limited"))
      (libsource (lib "Miscellaneous Devices") (part "Res2"))
    )
    (comp (ref "R109")
      (value "1K")
      (footprint "0805R")
      (description "Resistor")
      (fields (field (name "Comment") "Res2") (field (name "PUBLISHER") "Altium Limited"))
      (libsource (lib "") (part "Res2_1"))
    )
    (comp (ref "R110")
      (value "1K")
      (footprint "0805R")
      (description "Resistor")
      (fields (field (name "Comment") "Res2") (field (name "PUBLISHER") "Altium Limited"))
      (libsource (lib "") (part "Res2_1"))
    )
    (comp (ref "R111")
      (value "0")
      (footprint "0805R")
      (description "Resistor")
      (fields (field (name "Comment") "Res2") (field (name "PUBLISHER") "Altium Limited"))
      (libsource (lib "") (part "Res2_1"))
    )
    (comp (ref "R112")
      (value "10K")
      (footprint "0805R")
      (description "Resistor")
      (fields (field (name "Comment") "Res2") (field (name "PUBLISHER") "Altium Limited"))
      (libsource (lib "Miscellaneous Devices") (part "Res2"))
    )
    (comp (ref "R113")
      (value "0")
      (footprint "0805R")
      (description "Resistor")
      (fields (field (name "Comment") "Res2") (field (name "PUBLISHER") "Altium Limited"))
      (libsource (lib "") (part "Res2_2"))
    )
    (comp (ref "R114")
      (value "0")
      (footprint "0805R")
      (description "Resistor")
      (fields (field (name "Comment") "Res2") (field (name "PUBLISHER") "Altium Limited"))
      (libsource (lib "") (part "Res2_2"))
    )
    (comp (ref "R115")
      (value "0")
      (footprint "0805R")
      (description "Resistor")
      (fields (field (name "Comment") "Res2") (field (name "PUBLISHER") "Altium Limited"))
      (libsource (lib "") (part "Res2_1"))
    )
    (comp (ref "R116")
      (value "0")
      (footprint "0805R")
      (description "Resistor")
      (fields (field (name "Comment") "Res2") (field (name "PUBLISHER") "Altium Limited"))
      (libsource (lib "") (part "Res2_1"))
    )
    (comp (ref "R117")
      (value "10K")
      (footprint "0805R")
      (description "Resistor")
      (fields (field (name "Comment") "Res2") (field (name "PUBLISHER") "Altium Limited"))
      (libsource (lib "Miscellaneous Devices") (part "Res2"))
    )
    (comp (ref "R130")
      (value "10K")
      (footprint "0805R")
      (description "Resistor")
      (fields (field (name "Comment") "Res2") (field (name "PUBLISHER") "Altium Limited"))
      (libsource (lib "Miscellaneous Devices") (part "Res2"))
    )
    (comp (ref "R150")
      (value "10K")
      (footprint "0805R")
      (description "Resistor")
      (fields (field (name "Comment") "Res2") (field (name "PUBLISHER") "Altium Limited"))
      (libsource (lib "Miscellaneous Devices") (part "Res2"))
    )
    (comp (ref "R163")
      (value "10K")
      (footprint "0805R")
      (description "Resistor")
      (fields (field (name "Comment") "Res2") (field (name "PUBLISHER") "Altium Limited"))
      (libsource (lib "Miscellaneous Devices") (part "Res2"))
    )
    (comp (ref "R164")
      (value "10K")
      (footprint "0805R")
      (description "Resistor")
      (fields (field (name "Comment") "Res2") (field (name "PUBLISHER") "Altium Limited"))
      (libsource (lib "Miscellaneous Devices") (part "Res2"))
    )
    (comp (ref "R165")
      (value "10K")
      (footprint "0805R")
      (description "Resistor")
      (fields (field (name "Comment") "Res2") (field (name "PUBLISHER") "Altium Limited"))
      (libsource (lib "Miscellaneous Devices") (part "Res2"))
    )
    (comp (ref "R166")
      (value "10K")
      (footprint "0805R")
      (description "Resistor")
      (fields (field (name "Comment") "Res2") (field (name "PUBLISHER") "Altium Limited"))
      (libsource (lib "Miscellaneous Devices") (part "Res2"))
    )
    (comp (ref "R167")
      (value "10K")
      (footprint "0805R")
      (description "Resistor")
      (fields (field (name "Comment") "Res2") (field (name "PUBLISHER") "Altium Limited"))
      (libsource (lib "Miscellaneous Devices") (part "Res2"))
    )
    (comp (ref "R168")
      (value "10K")
      (footprint "0805R")
      (description "Resistor")
      (fields (field (name "Comment") "Res2") (field (name "PUBLISHER") "Altium Limited"))
      (libsource (lib "Miscellaneous Devices") (part "Res2"))
    )
    (comp (ref "R169")
      (value "10K")
      (footprint "0603AR")
      (description "Resistor")
      (fields (field (name "Comment") "Res2") (field (name "PUBLISHER") "Altium Limited"))
      (libsource (lib "Miscellaneous Devices") (part "Res2"))
    )
    (comp (ref "R170")
      (value "10K")
      (footprint "0603AR")
      (description "Resistor")
      (fields (field (name "Comment") "Res2") (field (name "PUBLISHER") "Altium Limited"))
      (libsource (lib "Miscellaneous Devices") (part "Res2"))
    )
    (comp (ref "R171")
      (value "10K")
      (footprint "0603AR")
      (description "Resistor")
      (fields (field (name "Comment") "Res2") (field (name "PUBLISHER") "Altium Limited"))
      (libsource (lib "") (part "Res2_1"))
    )
    (comp (ref "R175")
      (value "0")
      (footprint "0805R")
      (description "Resistor")
      (fields (field (name "Comment") "Res2") (field (name "PUBLISHER") "Altium Limited"))
      (libsource (lib "Miscellaneous Devices") (part "Res2"))
    )
    (comp (ref "SW2")
      (value "Header 3X2")
      (footprint "SW_6")
      (description "Header, 3-Pin, Dual row")
      (fields (field (name "PUBLISHER") "Altium Limited"))
      (libsource (lib "Miscellaneous Connectors") (part "Header 3X2"))
    )
    (comp (ref "U22") (value "ADUM5401") (footprint "SOL-16_L") (libsource (lib "ic_lib") (part "ADUM5401")))
    (comp (ref "U23")
      (value "OPA354")
      (footprint "IC:SOT23-5")
      (description "250MHz, Rail-to-Rail I/O, CMOS")
      (libsource (lib "IC") (part "OPA354"))
    )
    (comp (ref "U24")
      (value "OPA354")
      (footprint "IC:SOT23-5")
      (description "250MHz, Rail-to-Rail I/O, CMOS")
      (libsource (lib "IC") (part "OPA354"))
    )
    (comp (ref "U25")
      (value "OPA354")
      (footprint "IC:SOT23-5")
      (description "250MHz, Rail-to-Rail I/O, CMOS")
      (libsource (lib "IC") (part "OPA354"))
    )
    (comp (ref "U26")
      (value "OPA354")
      (footprint "IC:SOT23-5")
      (description "250MHz, Rail-to-Rail I/O, CMOS")
      (libsource (lib "IC") (part "OPA354"))
    )
    (comp (ref "U27") (value "AD7606") (footprint "TQFP64") (libsource (lib "AD7606V23A") (part "AD7606")))
    (comp (ref "U28") (value "ADUM151") (footprint "SO16NB") (libsource (lib "ic_lib") (part "ADUM151")))
    (comp (ref "U29") (value "REF5025") (footprint "MSOP8") (libsource (lib "AD7606V23A") (part "REF5025")))
    (comp (ref "U30") (value "AD5686") (footprint "TSSOP16") (libsource (lib "ic_lib") (part "AD5686")))
  )
  (nets
    (net (code "1") (name "+5V_2") (class "Default")
      (node (ref "C110") (pin "2") (pinfunction "2_2") (pintype "passive"))
      (node (ref "C118") (pin "2") (pinfunction "2_2") (pintype "passive"))
      (node (ref "C119") (pin "2") (pinfunction "2_2") (pintype "passive"))
      (node (ref "C120") (pin "2") (pinfunction "2_2") (pintype "passive"))
      (node (ref "C125") (pin "2") (pinfunction "2_2") (pintype "passive"))
      (node (ref "C127") (pin "2") (pinfunction "2_2") (pintype "passive"))
      (node (ref "C130") (pin "2") (pinfunction "2_2") (pintype "passive"))
      (node (ref "C131") (pin "2") (pinfunction "2_2") (pintype "passive"))
      (node (ref "C142") (pin "1") (pinfunction "1_1") (pintype "passive"))
      (node (ref "C143") (pin "1") (pinfunction "1_1") (pintype "passive"))
      (node (ref "C144") (pin "1") (pinfunction "1_1") (pintype "passive"))
      (node (ref "C145") (pin "1") (pinfunction "1_1") (pintype "passive"))
      (node (ref "C150") (pin "1") (pinfunction "1_1") (pintype "passive"))
      (node (ref "C153") (pin "2") (pinfunction "2_2") (pintype "passive"))
      (node (ref "C197") (pin "1") (pinfunction "1_1") (pintype "passive"))
      (node (ref "C203") (pin "1") (pinfunction "1_1") (pintype "passive"))
      (node (ref "U23") (pin "5") (pinfunction "V+_5") (pintype "power_in"))
      (node (ref "U24") (pin "5") (pinfunction "V+_5") (pintype "power_in"))
      (node (ref "U25") (pin "5") (pinfunction "V+_5") (pintype "power_in"))
      (node (ref "U26") (pin "5") (pinfunction "V+_5") (pintype "power_in"))
      (node (ref "U27") (pin "1") (pinfunction "AVCC_1") (pintype "passive"))
      (node (ref "U27") (pin "37") (pinfunction "AVCC_37") (pintype "passive"))
      (node (ref "U27") (pin "38") (pinfunction "AVCC_38") (pintype "passive"))
      (node (ref "U27") (pin "48") (pinfunction "AVCC_48") (pintype "passive"))
      (node (ref "U29") (pin "2") (pinfunction "Vin_2") (pintype "passive"))
      (node (ref "U30") (pin "5") (pinfunction "VDD_5") (pintype "passive"))
    )
    (net (code "2") (name "+6V_2") (class "Default")
      (node (ref "C155") (pin "1") (pinfunction "1_1") (pintype "passive"))
      (node (ref "C165") (pin "1") (pinfunction "1_1") (pintype "passive"))
      (node (ref "R169") (pin "1") (pinfunction "1_1") (pintype "passive"))
      (node (ref "U22") (pin "10") (pinfunction "VISO_10") (pintype "passive"))
      (node (ref "U28") (pin "16") (pinfunction "VDD2_16") (pintype "passive"))
    )
    (net (code "3") (name "/AN1") (class "Default")
      (node (ref "C121") (pin "2") (pinfunction "2_2") (pintype "passive"))
      (node (ref "C122") (pin "2") (pinfunction "2_2") (pintype "passive"))
      (node (ref "D18") (pin "2") (pinfunction "K_2") (pintype "passive"))
      (node (ref "P33") (pin "17") (pinfunction "17_17") (pintype "passive"))
      (node (ref "R35") (pin "2") (pinfunction "2_2") (pintype "passive"))
    )
    (net (code "4") (name "/AN2") (class "Default")
      (node (ref "C123") (pin "2") (pinfunction "2_2") (pintype "passive"))
      (node (ref "C124") (pin "2") (pinfunction "2_2") (pintype "passive"))
      (node (ref "D17") (pin "2") (pinfunction "K_2") (pintype "passive"))
      (node (ref "P33") (pin "19") (pinfunction "19_19") (pintype "passive"))
      (node (ref "R91") (pin "2") (pinfunction "2_2") (pintype "passive"))
    )
    (net (code "5") (name "/AN3") (class "Default")
      (node (ref "C128") (pin "2") (pinfunction "2_2") (pintype "passive"))
      (node (ref "C129") (pin "2") (pinfunction "2_2") (pintype "passive"))
      (node (ref "D19") (pin "2") (pinfunction "K_2") (pintype "passive"))
      (node (ref "P33") (pin "21") (pinfunction "21_21") (pintype "passive"))
      (node (ref "R98") (pin "2") (pinfunction "2_2") (pintype "passive"))
    )
    (net (code "6") (name "/AN4") (class "Default")
      (node (ref "C132") (pin "2") (pinfunction "2_2") (pintype "passive"))
      (node (ref "C133") (pin "2") (pinfunction "2_2") (pintype "passive"))
      (node (ref "D20") (pin "2") (pinfunction "K_2") (pintype "passive"))
      (node (ref "P33") (pin "23") (pinfunction "23_23") (pintype "passive"))
      (node (ref "R103") (pin "2") (pinfunction "2_2") (pintype "passive"))
    )
    (net (code "7") (name "/BUSY_1") (class "Default")
      (node (ref "A1") (pin "8") (pinfunction "8_8") (pintype "passive"))
      (node (ref "U27") (pin "14") (pinfunction "BUSY_14") (pintype "passive"))
    )
    (net (code "8") (name "/CLK_1") (class "Default")
      (node (ref "R112") (pin "1") (pinfunction "1_1") (pintype "passive"))
      (node (ref "U27") (pin "12") (pinfunction "~{RD}/SCLK_12") (pintype "passive"))
      (node (ref "U30") (pin "12") (pinfunction "SCLK_12") (pintype "passive"))
    )
    (net (code "9") (name "/CONVA_1") (class "Default")
      (node (ref "A1") (pin "4") (pinfunction "4_4") (pintype "passive"))
      (node (ref "U27") (pin "10") (pinfunction "CONVST_B_10") (pintype "passive"))
      (node (ref "U27") (pin "9") (pinfunction "CONVST_A_9") (pintype "passive"))
    )
    (net (code "10") (name "/CS_1") (class "Default")
      (node (ref "R130") (pin "1") (pinfunction "1_1") (pintype "passive"))
      (node (ref "U27") (pin "13") (pinfunction "~{CS}_13") (pintype "passive"))
    )
    (net (code "11") (name "/CS_2") (class "Default")
      (node (ref "R164") (pin "1") (pinfunction "1_1") (pintype "passive"))
      (node (ref "U30") (pin "13") (pinfunction "SYNC_13") (pintype "passive"))
    )
    (net (code "12") (name "/DA1") (class "Default")
      (node (ref "R65") (pin "1") (pinfunction "1_1") (pintype "passive"))
      (node (ref "U30") (pin "7") (pinfunction "OUTD_7") (pintype "passive"))
    )
    (net (code "13") (name "/DA2") (class "Default")
      (node (ref "R90") (pin "1") (pinfunction "1_1") (pintype "passive"))
      (node (ref "U30") (pin "6") (pinfunction "OUTC_6") (pintype "passive"))
    )
    (net (code "14") (name "/DA3") (class "Default")
      (node (ref "R97") (pin "1") (pinfunction "1_1") (pintype "passive"))
      (node (ref "U30") (pin "3") (pinfunction "OUTA_3") (pintype "passive"))
    )
    (net (code "15") (name "/DA4") (class "Default")
      (node (ref "R102") (pin "1") (pinfunction "1_1") (pintype "passive"))
      (node (ref "U30") (pin "2") (pinfunction "OUTB_2") (pintype "passive"))
    )
    (net (code "16") (name "/DI_1") (class "Default")
      (node (ref "R166") (pin "1") (pinfunction "1_1") (pintype "passive"))
      (node (ref "U30") (pin "14") (pinfunction "SDIN_14") (pintype "passive"))
    )
    (net (code "17") (name "/DOUTA_1") (class "Default")
      (node (ref "R113") (pin "2") (pinfunction "2_2") (pintype "passive"))
      (node (ref "U27") (pin "24") (pinfunction "DB7/DoutA_24") (pintype "passive"))
    )
    (net (code "18") (name "/DOUTB_1") (class "Default")
      (node (ref "R114") (pin "2") (pinfunction "2_2") (pintype "passive"))
      (node (ref "U27") (pin "25") (pinfunction "DB8/DoutB_25") (pintype "passive"))
    )
    (net (code "19") (name "/DO_1") (class "Default")
      (node (ref "R113") (pin "1") (pinfunction "1_1") (pintype "passive"))
      (node (ref "R114") (pin "1") (pinfunction "1_1") (pintype "passive"))
      (node (ref "R168") (pin "1") (pinfunction "1_1") (pintype "passive"))
    )
    (net (code "20") (name "/I1+") (class "Default")
      (node (ref "P33") (pin "1") (pinfunction "1_1") (pintype "passive"))
      (node (ref "R59") (pin "2") (pinfunction "2_2") (pintype "passive"))
      (node (ref "R96") (pin "2") (pinfunction "2_2") (pintype "passive"))
    )
    (net (code "21") (name "/I1-") (class "Default")
      (node (ref "P33") (pin "2") (pinfunction "2_2") (pintype "passive"))
      (node (ref "R59") (pin "1") (pinfunction "1_1") (pintype "passive"))
      (node (ref "R60") (pin "2") (pinfunction "2_2") (pintype "passive"))
      (node (ref "R61") (pin "2") (pinfunction "2_2") (pintype "passive"))
    )
    (net (code "22") (name "/I2+") (class "Default")
      (node (ref "P33") (pin "3") (pinfunction "3_3") (pintype "passive"))
      (node (ref "R62") (pin "2") (pinfunction "2_2") (pintype "passive"))
      (node (ref "R63") (pin "1") (pinfunction "1_1") (pintype "passive"))
    )
    (net (code "23") (name "/I2-") (class "Default")
      (node (ref "P33") (pin "4") (pinfunction "4_4") (pintype "passive"))
      (node (ref "R63") (pin "2") (pinfunction "2_2") (pintype "passive"))
      (node (ref "R64") (pin "2") (pinfunction "2_2") (pintype "passive"))
      (node (ref "R99") (pin "2") (pinfunction "2_2") (pintype "passive"))
    )
    (net (code "24") (name "/I3+") (class "Default")
      (node (ref "P33") (pin "5") (pinfunction "5_5") (pintype "passive"))
      (node (ref "R66") (pin "2") (pinfunction "2_2") (pintype "passive"))
      (node (ref "R67") (pin "1") (pinfunction "1_1") (pintype "passive"))
    )
    (net (code "25") (name "/I3-") (class "Default")
      (node (ref "P33") (pin "6") (pinfunction "6_6") (pintype "passive"))
      (node (ref "R67") (pin "2") (pinfunction "2_2") (pintype "passive"))
      (node (ref "R68") (pin "2") (pinfunction "2_2") (pintype "passive"))
      (node (ref "R69") (pin "2") (pinfunction "2_2") (pintype "passive"))
    )
    (net (code "26") (name "/I4+") (class "Default")
      (node (ref "P33") (pin "7") (pinfunction "7_7") (pintype "passive"))
      (node (ref "R70") (pin "2") (pinfunction "2_2") (pintype "passive"))
      (node (ref "R71") (pin "1") (pinfunction "1_1") (pintype "passive"))
    )
    (net (code "27") (name "/I4-") (class "Default")
      (node (ref "P33") (pin "8") (pinfunction "8_8") (pintype "passive"))
      (node (ref "R71") (pin "2") (pinfunction "2_2") (pintype "passive"))
      (node (ref "R72") (pin "2") (pinfunction "2_2") (pintype "passive"))
      (node (ref "R73") (pin "2") (pinfunction "2_2") (pintype "passive"))
    )
    (net (code "28") (name "/I5+") (class "Default")
      (node (ref "P33") (pin "9") (pinfunction "9_9") (pintype "passive"))
      (node (ref "R74") (pin "2") (pinfunction "2_2") (pintype "passive"))
      (node (ref "R75") (pin "1") (pinfunction "1_1") (pintype "passive"))
    )
    (net (code "29") (name "/I5-") (class "Default")
      (node (ref "P33") (pin "10") (pinfunction "10_10") (pintype "passive"))
      (node (ref "R75") (pin "2") (pinfunction "2_2") (pintype "passive"))
      (node (ref "R76") (pin "2") (pinfunction "2_2") (pintype "passive"))
      (node (ref "R77") (pin "2") (pinfunction "2_2") (pintype "passive"))
    )
    (net (code "30") (name "/I6+") (class "Default")
      (node (ref "P33") (pin "11") (pinfunction "11_11") (pintype "passive"))
      (node (ref "R78") (pin "2") (pinfunction "2_2") (pintype "passive"))
      (node (ref "R79") (pin "1") (pinfunction "1_1") (pintype "passive"))
    )
    (net (code "31") (name "/I6-") (class "Default")
      (node (ref "P33") (pin "12") (pinfunction "12_12") (pintype "passive"))
      (node (ref "R79") (pin "2") (pinfunction "2_2") (pintype "passive"))
      (node (ref "R80") (pin "2") (pinfunction "2_2") (pintype "passive"))
      (node (ref "R81") (pin "2") (pinfunction "2_2") (pintype "passive"))
    )
    (net (code "32") (name "/I7+") (class "Default")
      (node (ref "P33") (pin "13") (pinfunction "13_13") (pintype "passive"))
      (node (ref "R82") (pin "2") (pinfunction "2_2") (pintype "passive"))
      (node (ref "R83") (pin "1") (pinfunction "1_1") (pintype "passive"))
    )
    (net (code "33") (name "/I7-") (class "Default")
      (node (ref "P33") (pin "14") (pinfunction "14_14") (pintype "passive"))
      (node (ref "R83") (pin "2") (pinfunction "2_2") (pintype "passive"))
      (node (ref "R84") (pin "2") (pinfunction "2_2") (pintype "passive"))
      (node (ref "R85") (pin "2") (pinfunction "2_2") (pintype "passive"))
    )
    (net (code "34") (name "/I8+") (class "Default")
      (node (ref "P33") (pin "15") (pinfunction "15_15") (pintype "passive"))
      (node (ref "R86") (pin "2") (pinfunction "2_2") (pintype "passive"))
      (node (ref "R87") (pin "1") (pinfunction "1_1") (pintype "passive"))
    )
    (net (code "35") (name "/I8-") (class "Default")
      (node (ref "P33") (pin "16") (pinfunction "16_16") (pintype "passive"))
      (node (ref "R87") (pin "2") (pinfunction "2_2") (pintype "passive"))
      (node (ref "R88") (pin "2") (pinfunction "2_2") (pintype "passive"))
      (node (ref "R89") (pin "2") (pinfunction "2_2") (pintype "passive"))
    )
    (net (code "36") (name "/OS0_1") (class "Default")
      (node (ref "R108") (pin "2") (pinfunction "2_2") (pintype "passive"))
      (node (ref "SW2") (pin "2") (pinfunction "2_2") (pintype "passive"))
      (node (ref "U27") (pin "3") (pinfunction "OS0_3") (pintype "passive"))
    )
    (net (code "37") (name "/OS1_1") (class "Default")
      (node (ref "R107") (pin "2") (pinfunction "2_2") (pintype "passive"))
      (node (ref "SW2") (pin "4") (pinfunction "4_4") (pintype "passive"))
      (node (ref "U27") (pin "4") (pinfunction "OS1_4") (pintype "passive"))
    )
    (net (code "38") (name "/OS2_1") (class "Default")
      (node (ref "R106") (pin "2") (pinfunction "2_2") (pintype "passive"))
      (node (ref "SW2") (pin "6") (pinfunction "6_6") (pintype "passive"))
      (node (ref "U27") (pin "5") (pinfunction "OS2_5") (pintype "passive"))
    )
    (net (code "39") (name "/PART2_BUSY") (class "Default")
      (node (ref "A4") (pin "7") (pinfunction "7_7") (pintype "passive"))
    )
    (net (code "40") (name "/PART2_CLK") (class "Default")
      (node (ref "R23") (pin "2") (pinfunction "2_2") (pintype "passive"))
    )
    (net (code "41") (name "/PART2_CONV") (class "Default")
      (node (ref "A4") (pin "3") (pinfunction "3_3") (pintype "passive"))
    )
    (net (code "42") (name "/PART2_CS1") (class "Default")
      (node (ref "R117") (pin "2") (pinfunction "2_2") (pintype "passive"))
    )
    (net (code "43") (name "/PART2_CS2") (class "Default")
      (node (ref "R163") (pin "2") (pinfunction "2_2") (pintype "passive"))
    )
    (net (code "44") (name "/PART2_DI") (class "Default")
      (node (ref "R165") (pin "2") (pinfunction "2_2") (pintype "passive"))
    )
    (net (code "45") (name "/PART2_DO") (class "Default")
      (node (ref "R167") (pin "2") (pinfunction "2_2") (pintype "passive"))
    )
    (net (code "46") (name "/PART2_REST") (class "Default")
      (node (ref "A4") (pin "5") (pinfunction "5_5") (pintype "passive"))
    )
    (net (code "47") (name "/REFIN_1") (class "Default")
      (node (ref "C137") (pin "2") (pinfunction "2_2") (pintype "passive"))
      (node (ref "C138") (pin "1") (pinfunction "1_1") (pintype "passive"))
      (node (ref "C152") (pin "1") (pinfunction "1_1") (pintype "passive"))
      (node (ref "C25") (pin "1") (pinfunction "1_1") (pintype "passive"))
      (node (ref "U27") (pin "42") (pinfunction "REFIN/REFOUT_42") (pintype "passive"))
      (node (ref "U29") (pin "6") (pinfunction "Vout_6") (pintype "passive"))
      (node (ref "U30") (pin "1") (pinfunction "VREF_1") (pintype "passive"))
    )
    (net (code "48") (name "/REFSEL_1") (class "Default")
      (node (ref "R115") (pin "2") (pinfunction "2_2") (pintype "passive"))
      (node (ref "R116") (pin "2") (pinfunction "2_2") (pintype "passive"))
      (node (ref "U27") (pin "34") (pinfunction "REF_SELECT_34") (pintype "passive"))
    )
    (net (code "49") (name "/REST_1") (class "Default")
      (node (ref "A1") (pin "6") (pinfunction "8_6") (pintype "passive"))
      (node (ref "U27") (pin "11") (pinfunction "RESET_11") (pintype "passive"))
    )
    (net (code "50") (name "/V1+") (class "Default")
      (node (ref "C108") (pin "2") (pinfunction "2_2") (pintype "passive"))
      (node (ref "C109") (pin "2") (pinfunction "2_2") (pintype "passive"))
      (node (ref "R55") (pin "2") (pinfunction "2_2") (pintype "passive"))
      (node (ref "U27") (pin "49") (pinfunction "V1_49") (pintype "passive"))
    )
    (net (code "51") (name "/V1-") (class "Default")
      (node (ref "C108") (pin "1") (pinfunction "1_1") (pintype "passive"))
      (node (ref "C109") (pin "1") (pinfunction "1_1") (pintype "passive"))
      (node (ref "R57") (pin "2") (pinfunction "2_2") (pintype "passive"))
      (node (ref "U27") (pin "50") (pinfunction "V1GND_50") (pintype "passive"))
    )
    (net (code "52") (name "/V2+") (class "Default")
      (node (ref "C106") (pin "2") (pinfunction "2_2") (pintype "passive"))
      (node (ref "C107") (pin "2") (pinfunction "2_2") (pintype "passive"))
      (node (ref "R52") (pin "2") (pinfunction "2_2") (pintype "passive"))
      (node (ref "U27") (pin "51") (pinfunction "V2_51") (pintype "passive"))
    )
    (net (code "53") (name "/V2-") (class "Default")
      (node (ref "C106") (pin "1") (pinfunction "1_1") (pintype "passive"))
      (node (ref "C107") (pin "1") (pinfunction "1_1") (pintype "passive"))
      (node (ref "R54") (pin "2") (pinfunction "2_2") (pintype "passive"))
      (node (ref "U27") (pin "52") (pinfunction "V2GND_52") (pintype "passive"))
    )
    (net (code "54") (name "/V3+") (class "Default")
      (node (ref "C104") (pin "2") (pinfunction "2_2") (pintype "passive"))
      (node (ref "C105") (pin "2") (pinfunction "2_2") (pintype "passive"))
      (node (ref "R49") (pin "2") (pinfunction "2_2") (pintype "passive"))
      (node (ref "U27") (pin "53") (pinfunction "V3_53") (pintype "passive"))
    )
    (net (code "55") (name "/V3-") (class "Default")
      (node (ref "C104") (pin "1") (pinfunction "1_1") (pintype "passive"))
      (node (ref "C105") (pin "1") (pinfunction "1_1") (pintype "passive"))
      (node (ref "R51") (pin "2") (pinfunction "2_2") (pintype "passive"))
      (node (ref "U27") (pin "54") (pinfunction "V3GND_54") (pintype "passive"))
    )
    (net (code "56") (name "/V4+") (class "Default")
      (node (ref "C100") (pin "2") (pinfunction "2_2") (pintype "passive"))
      (node (ref "C102") (pin "2") (pinfunction "2_2") (pintype "passive"))
      (node (ref "R46") (pin "2") (pinfunction "2_2") (pintype "passive"))
      (node (ref "U27") (pin "55") (pinfunction "V4_55") (pintype "passive"))
    )
    (net (code "57") (name "/V4-") (class "Default")
      (node (ref "C100") (pin "1") (pinfunction "1_1") (pintype "passive"))
      (node (ref "C102") (pin "1") (pinfunction "1_1") (pintype "passive"))
      (node (ref "R48") (pin "2") (pinfunction "2_2") (pintype "passive"))
      (node (ref "U27") (pin "56") (pinfunction "V4GND_56") (pintype "passive"))
    )
    (net (code "58") (name "/V5+") (class "Default")
      (node (ref "C95") (pin "2") (pinfunction "2_2") (pintype "passive"))
      (node (ref "C96") (pin "2") (pinfunction "2_2") (pintype "passive"))
      (node (ref "R43") (pin "2") (pinfunction "2_2") (pintype "passive"))
      (node (ref "U27") (pin "57") (pinfunction "V5_57") (pintype "passive"))
    )
    (net (code "59") (name "/V5-") (class "Default")
      (node (ref "C95") (pin "1") (pinfunction "1_1") (pintype "passive"))
      (node (ref "C96") (pin "1") (pinfunction "1_1") (pintype "passive"))
      (node (ref "R45") (pin "2") (pinfunction "2_2") (pintype "passive"))
      (node (ref "U27") (pin "58") (pinfunction "V5GND_58") (pintype "passive"))
    )
    (net (code "60") (name "/V6+") (class "Default")
      (node (ref "C71") (pin "2") (pinfunction "2_2") (pintype "passive"))
      (node (ref "C94") (pin "2") (pinfunction "2_2") (pintype "passive"))
      (node (ref "R40") (pin "2") (pinfunction "2_2") (pintype "passive"))
      (node (ref "U27") (pin "59") (pinfunction "V6_59") (pintype "passive"))
    )
    (net (code "61") (name "/V6-") (class "Default")
      (node (ref "C71") (pin "1") (pinfunction "1_1") (pintype "passive"))
      (node (ref "C94") (pin "1") (pinfunction "1_1") (pintype "passive"))
      (node (ref "R42") (pin "2") (pinfunction "2_2") (pintype "passive"))
      (node (ref "U27") (pin "60") (pinfunction "V6GND_60") (pintype "passive"))
    )
    (net (code "62") (name "/V7+") (class "Default")
      (node (ref "C65") (pin "2") (pinfunction "2_2") (pintype "passive"))
      (node (ref "C67") (pin "2") (pinfunction "2_2") (pintype "passive"))
      (node (ref "R37") (pin "2") (pinfunction "2_2") (pintype "passive"))
      (node (ref "U27") (pin "61") (pinfunction "V7_61") (pintype "passive"))
    )
    (net (code "63") (name "/V7-") (class "Default")
      (node (ref "C65") (pin "1") (pinfunction "1_1") (pintype "passive"))
      (node (ref "C67") (pin "1") (pinfunction "1_1") (pintype "passive"))
      (node (ref "R39") (pin "2") (pinfunction "2_2") (pintype "passive"))
      (node (ref "U27") (pin "62") (pinfunction "V7GND_62") (pintype "passive"))
    )
    (net (code "64") (name "/V8+") (class "Default")
      (node (ref "C41") (pin "2") (pinfunction "2_2") (pintype "passive"))
      (node (ref "C56") (pin "2") (pinfunction "2_2") (pintype "passive"))
      (node (ref "R30") (pin "2") (pinfunction "2_2") (pintype "passive"))
      (node (ref "U27") (pin "63") (pinfunction "V8_63") (pintype "passive"))
    )
    (net (code "65") (name "/V8-") (class "Default")
      (node (ref "C41") (pin "1") (pinfunction "1_1") (pintype "passive"))
      (node (ref "C56") (pin "1") (pinfunction "1_1") (pintype "passive"))
      (node (ref "R36") (pin "2") (pinfunction "2_2") (pintype "passive"))
      (node (ref "U27") (pin "64") (pinfunction "V8GND_64") (pintype "passive"))
    )
    (net (code "66") (name "5V_0") (class "Default")
      (node (ref "C139") (pin "2") (pinfunction "2_2") (pintype "passive"))
      (node (ref "C176") (pin "1") (pinfunction "1_1") (pintype "passive"))
      (node (ref "C177") (pin "1") (pinfunction "1_1") (pintype "passive"))
      (node (ref "C178") (pin "1") (pinfunction "1_1") (pintype "passive"))
      (node (ref "U22") (pin "1") (pinfunction "VDD1_1") (pintype "passive"))
      (node (ref "U28") (pin "1") (pinfunction "VDD1_1") (pintype "passive"))
    )
    (net (code "67") (name "AGND_2") (class "Default")
      (node (ref "C110") (pin "1") (pinfunction "1_1") (pintype "passive"))
      (node (ref "C118") (pin "1") (pinfunction "1_1") (pintype "passive"))
      (node (ref "C119") (pin "1") (pinfunction "1_1") (pintype "passive"))
      (node (ref "C120") (pin "1") (pinfunction "1_1") (pintype "passive"))
      (node (ref "C121") (pin "1") (pinfunction "1_1") (pintype "passive"))
      (node (ref "C122") (pin "1") (pinfunction "1_1") (pintype "passive"))
      (node (ref "C123") (pin "1") (pinfunction "1_1") (pintype "passive"))
      (node (ref "C124") (pin "1") (pinfunction "1_1") (pintype "passive"))
      (node (ref "C125") (pin "1") (pinfunction "1_1") (pintype "passive"))
      (node (ref "C127") (pin "1") (pinfunction "1_1") (pintype "passive"))
      (node (ref "C128") (pin "1") (pinfunction "1_1") (pintype "passive"))
      (node (ref "C129") (pin "1") (pinfunction "1_1") (pintype "passive"))
      (node (ref "C130") (pin "1") (pinfunction "1_1") (pintype "passive"))
      (node (ref "C131") (pin "1") (pinfunction "1_1") (pintype "passive"))
      (node (ref "C132") (pin "1") (pinfunction "1_1") (pintype "passive"))
      (node (ref "C133") (pin "1") (pinfunction "1_1") (pintype "passive"))
      (node (ref "C137") (pin "1") (pinfunction "1_1") (pintype "passive"))
      (node (ref "C138") (pin "2") (pinfunction "2_2") (pintype "passive"))
      (node (ref "C142") (pin "2") (pinfunction "2_2") (pintype "passive"))
      (node (ref "C143") (pin "2") (pinfunction "2_2") (pintype "passive"))
      (node (ref "C144") (pin "2") (pinfunction "2_2") (pintype "passive"))
      (node (ref "C145") (pin "2") (pinfunction "2_2") (pintype "passive"))
      (node (ref "C147") (pin "2") (pinfunction "2_2") (pintype "passive"))
      (node (ref "C148") (pin "2") (pinfunction "2_2") (pintype "passive"))
      (node (ref "C149") (pin "2") (pinfunction "2_2") (pintype "passive"))
      (node (ref "C150") (pin "2") (pinfunction "2_2") (pintype "passive"))
      (node (ref "C152") (pin "2") (pinfunction "2_2") (pintype "passive"))
      (node (ref "C153") (pin "1") (pinfunction "1_1") (pintype "passive"))
      (node (ref "C167") (pin "2") (pinfunction "2_2") (pintype "passive"))
      (node (ref "C171") (pin "2") (pinfunction "2_2") (pintype "passive"))
      (node (ref "C173") (pin "2") (pinfunction "2_2") (pintype "passive"))
      (node (ref "C197") (pin "2") (pinfunction "2_2") (pintype "passive"))
      (node (ref "C201") (pin "2") (pinfunction "2_2") (pintype "passive"))
      (node (ref "C202") (pin "2") (pinfunction "2_2") (pintype "passive"))
      (node (ref "C203") (pin "2") (pinfunction "2_2") (pintype "passive"))
      (node (ref "C204") (pin "2") (pinfunction "2_2") (pintype "passive"))
      (node (ref "C25") (pin "2") (pinfunction "2_2") (pintype "passive"))
      (node (ref "D17") (pin "1") (pinfunction "A_1") (pintype "passive"))
      (node (ref "D18") (pin "1") (pinfunction "A_1") (pintype "passive"))
      (node (ref "D19") (pin "1") (pinfunction "A_1") (pintype "passive"))
      (node (ref "D20") (pin "1") (pinfunction "A_1") (pintype "passive"))
      (node (ref "P33") (pin "18") (pinfunction "18_18") (pintype "passive"))
      (node (ref "P33") (pin "20") (pinfunction "20_20") (pintype "passive"))
      (node (ref "P33") (pin "22") (pinfunction "22_22") (pintype "passive"))
      (node (ref "P33") (pin "24") (pinfunction "24_24") (pintype "passive"))
      (node (ref "P33") (pin "25") (pinfunction "25_25") (pintype "passive"))
      (node (ref "P33") (pin "26") (pinfunction "26_26") (pintype "passive"))
      (node (ref "R101") (pin "2") (pinfunction "2_2") (pintype "passive"))
      (node (ref "R105") (pin "2") (pinfunction "2_2") (pintype "passive"))
      (node (ref "R111") (pin "2") (pinfunction "2_2") (pintype "passive"))
      (node (ref "R115") (pin "1") (pinfunction "1_1") (pintype "passive"))
      (node (ref "R175") (pin "2") (pinfunction "2_2") (pintype "passive"))
      (node (ref "R61") (pin "1") (pinfunction "1_1") (pintype "passive"))
      (node (ref "R69") (pin "1") (pinfunction "1_1") (pintype "passive"))
      (node (ref "R73") (pin "1") (pinfunction "1_1") (pintype "passive"))
      (node (ref "R77") (pin "1") (pinfunction "1_1") (pintype "passive"))
      (node (ref "R81") (pin "1") (pinfunction "1_1") (pintype "passive"))
      (node (ref "R85") (pin "1") (pinfunction "1_1") (pintype "passive"))
      (node (ref "R89") (pin "1") (pinfunction "1_1") (pintype "passive"))
      (node (ref "R93") (pin "2") (pinfunction "2_2") (pintype "passive"))
      (node (ref "R95") (pin "2") (pinfunction "2_2") (pintype "passive"))
      (node (ref "R99") (pin "1") (pinfunction "1_1") (pintype "passive"))
      (node (ref "SW2") (pin "1") (pinfunction "1_1") (pintype "passive"))
      (node (ref "SW2") (pin "3") (pinfunction "3_3") (pintype "passive"))
      (node (ref "SW2") (pin "5") (pinfunction "5_5") (pintype "passive"))
      (node (ref "U23") (pin "2") (pinfunction "V-_2") (pintype "power_in"))
      (node (ref "U24") (pin "2") (pinfunction "V-_2") (pintype "power_in"))
      (node (ref "U25") (pin "2") (pinfunction "V-_2") (pintype "power_in"))
      (node (ref "U26") (pin "2") (pinfunction "V-_2") (pintype "power_in"))
      (node (ref "U27") (pin "16") (pinfunction "DB0_16") (pintype "passive"))
      (node (ref "U27") (pin "17") (pinfunction "DB1_17") (pintype "passive"))
      (node (ref "U27") (pin "18") (pinfunction "DB2_18") (pintype "passive"))
      (node (ref "U27") (pin "19") (pinfunction "DB3_19") (pintype "passive"))
      (node (ref "U27") (pin "2") (pinfunction "AGND_2") (pintype "passive"))
      (node (ref "U27") (pin "20") (pinfunction "DB4_20") (pintype "passive"))
      (node (ref "U27") (pin "21") (pinfunction "DB5_21") (pintype "passive"))
      (node (ref "U27") (pin "22") (pinfunction "DB6_22") (pintype "passive"))
      (node (ref "U27") (pin "26") (pinfunction "AGND_26") (pintype "passive"))
      (node (ref "U27") (pin "27") (pinfunction "DB9_27") (pintype "passive"))
      (node (ref "U27") (pin "28") (pinfunction "DB10_28") (pintype "passive"))
      (node (ref "U27") (pin "29") (pinfunction "DB11_29") (pintype "passive"))
      (node (ref "U27") (pin "30") (pinfunction "DB12_30") (pintype "passive"))
      (node (ref "U27") (pin "31") (pinfunction "DB13_31") (pintype "passive"))
      (node (ref "U27") (pin "32") (pinfunction "DB14/HBEN_32") (pintype "passive"))
      (node (ref "U27") (pin "33") (pinfunction "DB15/BYTE_SEL_33") (pintype "passive"))
      (node (ref "U27") (pin "35") (pinfunction "AGND_35") (pintype "passive"))
      (node (ref "U27") (pin "40") (pinfunction "AGND_40") (pintype "passive"))
      (node (ref "U27") (pin "41") (pinfunction "AGND_41") (pintype "passive"))
      (node (ref "U27") (pin "43") (pinfunction "REFGND_43") (pintype "passive"))
      (node (ref "U27") (pin "46") (pinfunction "REFGND_46") (pintype "passive"))
      (node (ref "U27") (pin "47") (pinfunction "AGND_47") (pintype "passive"))
      (node (ref "U29") (pin "4") (pinfunction "GND_4") (pintype "passive"))
      (node (ref "U30") (pin "16") (pinfunction "RSTSEL_16") (pintype "passive"))
      (node (ref "U30") (pin "4") (pinfunction "GND_4") (pintype "passive"))
      (node (ref "U30") (pin "9") (pinfunction "LDAC_9") (pintype "passive"))
    )
    (net (code "68") (name "DGND_2") (class "Default")
      (node (ref "C155") (pin "2") (pinfunction "2_2") (pintype "passive"))
      (node (ref "C165") (pin "2") (pinfunction "2_2") (pintype "passive"))
      (node (ref "C201") (pin "1") (pinfunction "1_1") (pintype "passive"))
      (node (ref "C202") (pin "1") (pinfunction "1_1") (pintype "passive"))
      (node (ref "R170") (pin "1") (pinfunction "1_1") (pintype "passive"))
      (node (ref "R171") (pin "2") (pinfunction "2_2") (pintype "passive"))
      (node (ref "R175") (pin "1") (pinfunction "1_1") (pintype "passive"))
      (node (ref "U28") (pin "9") (pinfunction "GND2_9") (pintype "passive"))
    )
    (net (code "69") (name "DVCC_2") (class "Default")
      (node (ref "C167") (pin "1") (pinfunction "1_1") (pintype "passive"))
      (node (ref "C171") (pin "1") (pinfunction "1_1") (pintype "passive"))
      (node (ref "C173") (pin "1") (pinfunction "1_1") (pintype "passive"))
      (node (ref "C204") (pin "1") (pinfunction "1_1") (pintype "passive"))
      (node (ref "R106") (pin "1") (pinfunction "1_1") (pintype "passive"))
      (node (ref "R107") (pin "1") (pinfunction "1_1") (pintype "passive"))
      (node (ref "R108") (pin "1") (pinfunction "1_1") (pintype "passive"))
      (node (ref "R109") (pin "2") (pinfunction "2_2") (pintype "passive"))
      (node (ref "R110") (pin "2") (pinfunction "2_2") (pintype "passive"))
      (node (ref "R116") (pin "1") (pinfunction "1_1") (pintype "passive"))
      (node (ref "R150") (pin "1") (pinfunction "1_1") (pintype "passive"))
      (node (ref "R6") (pin "2") (pinfunction "2_2") (pintype "passive"))
      (node (ref "U27") (pin "23") (pinfunction "VDRIVE_23") (pintype "passive"))
      (node (ref "U30") (pin "11") (pinfunction "VLOGIC_11") (pintype "passive"))
    )
    (net (code "70") (name "GND") (class "Default")
      (node (ref "C139") (pin "1") (pinfunction "1_1") (pintype "passive"))
      (node (ref "C176") (pin "2") (pinfunction "2_2") (pintype "passive"))
      (node (ref "C177") (pin "2") (pinfunction "2_2") (pintype "passive"))
      (node (ref "C178") (pin "2") (pinfunction "2_2") (pintype "passive"))
      (node (ref "U22") (pin "2") (pinfunction "GND1_2") (pintype "passive"))
      (node (ref "U22") (pin "8") (pinfunction "GND1_8") (pintype "passive"))
      (node (ref "U28") (pin "8") (pinfunction "GND1_8") (pintype "passive"))
    )
    (net (code "71") (name "Net-(C148-Pad1)") (class "Default")
      (node (ref "C148") (pin "1") (pinfunction "1_1") (pintype "passive"))
      (node (ref "U27") (pin "39") (pinfunction "REGCAP_39") (pintype "passive"))
    )
    (net (code "72") (name "Net-(C149-Pad1)") (class "Default")
      (node (ref "C149") (pin "1") (pinfunction "1_1") (pintype "passive"))
      (node (ref "U27") (pin "36") (pinfunction "REGCAP_36") (pintype "passive"))
    )
    (net (code "73") (name "Net-(D8-A)") (class "Default")
      (node (ref "C126") (pin "1") (pinfunction "1_1") (pintype "passive"))
      (node (ref "D8") (pin "1") (pinfunction "A_1") (pintype "passive"))
      (node (ref "R36") (pin "1") (pinfunction "1_1") (pintype "passive"))
      (node (ref "R58") (pin "1") (pinfunction "1_1") (pintype "passive"))
      (node (ref "R60") (pin "1") (pinfunction "1_1") (pintype "passive"))
    )
    (net (code "74") (name "Net-(D8-K)") (class "Default")
      (node (ref "C126") (pin "2") (pinfunction "2_2") (pintype "passive"))
      (node (ref "D8") (pin "2") (pinfunction "K_2") (pintype "passive"))
      (node (ref "R30") (pin "1") (pinfunction "1_1") (pintype "passive"))
      (node (ref "R58") (pin "2") (pinfunction "2_2") (pintype "passive"))
      (node (ref "R96") (pin "1") (pinfunction "1_1") (pintype "passive"))
    )
    (net (code "75") (name "Net-(D10-A)") (class "Default")
      (node (ref "C111") (pin "1") (pinfunction "1_1") (pintype "passive"))
      (node (ref "D10") (pin "1") (pinfunction "A_1") (pintype "passive"))
      (node (ref "R38") (pin "2") (pinfunction "2_2") (pintype "passive"))
      (node (ref "R39") (pin "1") (pinfunction "1_1") (pintype "passive"))
      (node (ref "R64") (pin "1") (pinfunction "1_1") (pintype "passive"))
    )
    (net (code "76") (name "Net-(D10-K)") (class "Default")
      (node (ref "C111") (pin "2") (pinfunction "2_2") (pintype "passive"))
      (node (ref "D10") (pin "2") (pinfunction "K_2") (pintype "passive"))
      (node (ref "R37") (pin "1") (pinfunction "1_1") (pintype "passive"))
      (node (ref "R38") (pin "1") (pinfunction "1_1") (pintype "passive"))
      (node (ref "R62") (pin "1") (pinfunction "1_1") (pintype "passive"))
    )
    (net (code "77") (name "Net-(D11-A)") (class "Default")
      (node (ref "C112") (pin "1") (pinfunction "1_1") (pintype "passive"))
      (node (ref "D11") (pin "1") (pinfunction "A_1") (pintype "passive"))
      (node (ref "R41") (pin "2") (pinfunction "2_2") (pintype "passive"))
      (node (ref "R42") (pin "1") (pinfunction "1_1") (pintype "passive"))
      (node (ref "R68") (pin "1") (pinfunction "1_1") (pintype "passive"))
    )
    (net (code "78") (name "Net-(D11-K)") (class "Default")
      (node (ref "C112") (pin "2") (pinfunction "2_2") (pintype "passive"))
      (node (ref "D11") (pin "2") (pinfunction "K_2") (pintype "passive"))
      (node (ref "R40") (pin "1") (pinfunction "1_1") (pintype "passive"))
      (node (ref "R41") (pin "1") (pinfunction "1_1") (pintype "passive"))
      (node (ref "R66") (pin "1") (pinfunction "1_1") (pintype "passive"))
    )
    (net (code "79") (name "Net-(D12-A)") (class "Default")
      (node (ref "C113") (pin "1") (pinfunction "1_1") (pintype "passive"))
      (node (ref "D12") (pin "1") (pinfunction "A_1") (pintype "passive"))
      (node (ref "R44") (pin "2") (pinfunction "2_2") (pintype "passive"))
      (node (ref "R45") (pin "1") (pinfunction "1_1") (pintype "passive"))
      (node (ref "R72") (pin "1") (pinfunction "1_1") (pintype "passive"))
    )
    (net (code "80") (name "Net-(D12-K)") (class "Default")
      (node (ref "C113") (pin "2") (pinfunction "2_2") (pintype "passive"))
      (node (ref "D12") (pin "2") (pinfunction "K_2") (pintype "passive"))
      (node (ref "R43") (pin "1") (pinfunction "1_1") (pintype "passive"))
      (node (ref "R44") (pin "1") (pinfunction "1_1") (pintype "passive"))
      (node (ref "R70") (pin "1") (pinfunction "1_1") (pintype "passive"))
    )
    (net (code "81") (name "Net-(D13-A)") (class "Default")
      (node (ref "C114") (pin "1") (pinfunction "1_1") (pintype "passive"))
      (node (ref "D13") (pin "1") (pinfunction "A_1") (pintype "passive"))
      (node (ref "R47") (pin "2") (pinfunction "2_2") (pintype "passive"))
      (node (ref "R48") (pin "1") (pinfunction "1_1") (pintype "passive"))
      (node (ref "R76") (pin "1") (pinfunction "1_1") (pintype "passive"))
    )
    (net (code "82") (name "Net-(D13-K)") (class "Default")
      (node (ref "C114") (pin "2") (pinfunction "2_2") (pintype "passive"))
      (node (ref "D13") (pin "2") (pinfunction "K_2") (pintype "passive"))
      (node (ref "R46") (pin "1") (pinfunction "1_1") (pintype "passive"))
      (node (ref "R47") (pin "1") (pinfunction "1_1") (pintype "passive"))
      (node (ref "R74") (pin "1") (pinfunction "1_1") (pintype "passive"))
    )
    (net (code "83") (name "Net-(D14-A)") (class "Default")
      (node (ref "C115") (pin "1") (pinfunction "1_1") (pintype "passive"))
      (node (ref "D14") (pin "1") (pinfunction "A_1") (pintype "passive"))
      (node (ref "R50") (pin "2") (pinfunction "2_2") (pintype "passive"))
      (node (ref "R51") (pin "1") (pinfunction "1_1") (pintype "passive"))
      (node (ref "R80") (pin "1") (pinfunction "1_1") (pintype "passive"))
    )
    (net (code "84") (name "Net-(D14-K)") (class "Default")
      (node (ref "C115") (pin "2") (pinfunction "2_2") (pintype "passive"))
      (node (ref "D14") (pin "2") (pinfunction "K_2") (pintype "passive"))
      (node (ref "R49") (pin "1") (pinfunction "1_1") (pintype "passive"))
      (node (ref "R50") (pin "1") (pinfunction "1_1") (pintype "passive"))
      (node (ref "R78") (pin "1") (pinfunction "1_1") (pintype "passive"))
    )
    (net (code "85") (name "Net-(D15-A)") (class "Default")
      (node (ref "C116") (pin "1") (pinfunction "1_1") (pintype "passive"))
      (node (ref "D15") (pin "1") (pinfunction "A_1") (pintype "passive"))
      (node (ref "R53") (pin "2") (pinfunction "2_2") (pintype "passive"))
      (node (ref "R54") (pin "1") (pinfunction "1_1") (pintype "passive"))
      (node (ref "R84") (pin "1") (pinfunction "1_1") (pintype "passive"))
    )
    (net (code "86") (name "Net-(D15-K)") (class "Default")
      (node (ref "C116") (pin "2") (pinfunction "2_2") (pintype "passive"))
      (node (ref "D15") (pin "2") (pinfunction "K_2") (pintype "passive"))
      (node (ref "R52") (pin "1") (pinfunction "1_1") (pintype "passive"))
      (node (ref "R53") (pin "1") (pinfunction "1_1") (pintype "passive"))
      (node (ref "R82") (pin "1") (pinfunction "1_1") (pintype "passive"))
    )
    (net (code "87") (name "Net-(D16-A)") (class "Default")
      (node (ref "C117") (pin "1") (pinfunction "1_1") (pintype "passive"))
      (node (ref "D16") (pin "1") (pinfunction "A_1") (pintype "passive"))
      (node (ref "R56") (pin "2") (pinfunction "2_2") (pintype "passive"))
      (node (ref "R57") (pin "1") (pinfunction "1_1") (pintype "passive"))
      (node (ref "R88") (pin "1") (pinfunction "1_1") (pintype "passive"))
    )
    (net (code "88") (name "Net-(D16-K)") (class "Default")
      (node (ref "C117") (pin "2") (pinfunction "2_2") (pintype "passive"))
      (node (ref "D16") (pin "2") (pinfunction "K_2") (pintype "passive"))
      (node (ref "R55") (pin "1") (pinfunction "1_1") (pintype "passive"))
      (node (ref "R56") (pin "1") (pinfunction "1_1") (pintype "passive"))
      (node (ref "R86") (pin "1") (pinfunction "1_1") (pintype "passive"))
    )
    (net (code "89") (name "Net-(R169-Pad2)") (class "Default")
      (node (ref "R169") (pin "2") (pinfunction "2_2") (pintype "passive"))
      (node (ref "U22") (pin "16") (pinfunction "VISO_16") (pintype "passive"))
    )
    (net (code "90") (name "Net-(R170-Pad2)") (class "Default")
      (node (ref "R170") (pin "2") (pinfunction "2_2") (pintype "passive"))
      (node (ref "U22") (pin "15") (pinfunction "GNDISO_15") (pintype "passive"))
    )
    (net (code "91") (name "Net-(R171-Pad1)") (class "Default")
      (node (ref "R171") (pin "1") (pinfunction "1_1") (pintype "passive"))
      (node (ref "U22") (pin "9") (pinfunction "GNDISO_9") (pintype "passive"))
    )
    (net (code "92") (name "Net-(U22-VIA)") (class "Default")
      (node (ref "A4") (pin "2") (pinfunction "2_2") (pintype "passive"))
      (node (ref "U22") (pin "3") (pinfunction "VIA_3") (pintype "passive"))
    )
    (net (code "93") (name "Net-(U22-VIB)") (class "Default")
      (node (ref "A4") (pin "4") (pinfunction "4_4") (pintype "passive"))
      (node (ref "U22") (pin "4") (pinfunction "VIB_4") (pintype "passive"))
    )
    (net (code "94") (name "Net-(U22-VIC)") (class "Default")
      (node (ref "A4") (pin "6") (pinfunction "8_6") (pintype "passive"))
      (node (ref "U22") (pin "5") (pinfunction "VIC_5") (pintype "passive"))
    )
    (net (code "95") (name "Net-(U22-VID)") (class "Default")
      (node (ref "A1") (pin "7") (pinfunction "7_7") (pintype "passive"))
      (node (ref "U22") (pin "11") (pinfunction "VID_11") (pintype "passive"))
    )
    (net (code "96") (name "Net-(U22-VOA)") (class "Default")
      (node (ref "A1") (pin "1") (pinfunction "1_1") (pintype "passive"))
      (node (ref "U22") (pin "14") (pinfunction "VOA_14") (pintype "passive"))
    )
    (net (code "97") (name "Net-(U22-VOB)") (class "Default")
      (node (ref "A1") (pin "3") (pinfunction "3_3") (pintype "passive"))
      (node (ref "U22") (pin "13") (pinfunction "VOB_13") (pintype "passive"))
    )
    (net (code "98") (name "Net-(U22-VOC)") (class "Default")
      (node (ref "A1") (pin "5") (pinfunction "5_5") (pintype "passive"))
      (node (ref "U22") (pin "12") (pinfunction "VOC_12") (pintype "passive"))
    )
    (net (code "99") (name "Net-(U22-VOD)") (class "Default")
      (node (ref "A4") (pin "8") (pinfunction "8_8") (pintype "passive"))
      (node (ref "U22") (pin "6") (pinfunction "VOD_6") (pintype "passive"))
    )
    (net (code "100") (name "Net-(U23-+)") (class "Default")
      (node (ref "R65") (pin "2") (pinfunction "2_2") (pintype "passive"))
      (node (ref "U23") (pin "3") (pinfunction "+_3") (pintype "power_in"))
    )
    (net (code "101") (name "Net-(U23--)") (class "Default")
      (node (ref "R92") (pin "2") (pinfunction "2_2") (pintype "passive"))
      (node (ref "R93") (pin "1") (pinfunction "1_1") (pintype "passive"))
      (node (ref "U23") (pin "4") (pinfunction "-_4") (pintype "power_in"))
    )
    (net (code "102") (name "Net-(U23-OUT)") (class "Default")
      (node (ref "R35") (pin "1") (pinfunction "1_1") (pintype "passive"))
      (node (ref "R92") (pin "1") (pinfunction "1_1") (pintype "passive"))
      (node (ref "U23") (pin "1") (pinfunction "OUT_1") (pintype "power_in"))
    )
    (net (code "103") (name "Net-(U24-+)") (class "Default")
      (node (ref "R90") (pin "2") (pinfunction "2_2") (pintype "passive"))
      (node (ref "U24") (pin "3") (pinfunction "+_3") (pintype "power_in"))
    )
    (net (code "104") (name "Net-(U24--)") (class "Default")
      (node (ref "R94") (pin "2") (pinfunction "2_2") (pintype "passive"))
      (node (ref "R95") (pin "1") (pinfunction "1_1") (pintype "passive"))
      (node (ref "U24") (pin "4") (pinfunction "-_4") (pintype "power_in"))
    )
    (net (code "105") (name "Net-(U24-OUT)") (class "Default")
      (node (ref "R91") (pin "1") (pinfunction "1_1") (pintype "passive"))
      (node (ref "R94") (pin "1") (pinfunction "1_1") (pintype "passive"))
      (node (ref "U24") (pin "1") (pinfunction "OUT_1") (pintype "power_in"))
    )
    (net (code "106") (name "Net-(U25-+)") (class "Default")
      (node (ref "R97") (pin "2") (pinfunction "2_2") (pintype "passive"))
      (node (ref "U25") (pin "3") (pinfunction "+_3") (pintype "power_in"))
    )
    (net (code "107") (name "Net-(U25--)") (class "Default")
      (node (ref "R100") (pin "2") (pinfunction "2_2") (pintype "passive"))
      (node (ref "R101") (pin "1") (pinfunction "1_1") (pintype "passive"))
      (node (ref "U25") (pin "4") (pinfunction "-_4") (pintype "power_in"))
    )
    (net (code "108") (name "Net-(U25-OUT)") (class "Default")
      (node (ref "R100") (pin "1") (pinfunction "1_1") (pintype "passive"))
      (node (ref "R98") (pin "1") (pinfunction "1_1") (pintype "passive"))
      (node (ref "U25") (pin "1") (pinfunction "OUT_1") (pintype "power_in"))
    )
    (net (code "109") (name "Net-(U26-+)") (class "Default")
      (node (ref "R102") (pin "2") (pinfunction "2_2") (pintype "passive"))
      (node (ref "U26") (pin "3") (pinfunction "+_3") (pintype "power_in"))
    )
    (net (code "110") (name "Net-(U26--)") (class "Default")
      (node (ref "R104") (pin "2") (pinfunction "2_2") (pintype "passive"))
      (node (ref "R105") (pin "1") (pinfunction "1_1") (pintype "passive"))
      (node (ref "U26") (pin "4") (pinfunction "-_4") (pintype "power_in"))
    )
    (net (code "111") (name "Net-(U26-OUT)") (class "Default")
      (node (ref "R103") (pin "1") (pinfunction "1_1") (pintype "passive"))
      (node (ref "R104") (pin "1") (pinfunction "1_1") (pintype "passive"))
      (node (ref "U26") (pin "1") (pinfunction "OUT_1") (pintype "power_in"))
    )
    (net (code "112") (name "Net-(U27-RANGE)") (class "Default")
      (node (ref "R111") (pin "1") (pinfunction "1_1") (pintype "passive"))
      (node (ref "R6") (pin "1") (pinfunction "1_1") (pintype "passive"))
      (node (ref "U27") (pin "8") (pinfunction "RANGE_8") (pintype "passive"))
    )
    (net (code "113") (name "Net-(U27-REFCAPA)") (class "Default")
      (node (ref "C147") (pin "1") (pinfunction "1_1") (pintype "passive"))
      (node (ref "U27") (pin "44") (pinfunction "REFCAPA_44") (pintype "passive"))
      (node (ref "U27") (pin "45") (pinfunction "REFCAPB_45") (pintype "passive"))
    )
    (net (code "114") (name "Net-(U27-~{PAR}{slash}SER{slash}BYTE_SEL)") (class "Default")
      (node (ref "R109") (pin "1") (pinfunction "1_1") (pintype "passive"))
      (node (ref "U27") (pin "6") (pinfunction "~{PAR}/SER/BYTE_SEL_6") (pintype "passive"))
    )
    (net (code "115") (name "Net-(U27-~{STBY})") (class "Default")
      (node (ref "R110") (pin "1") (pinfunction "1_1") (pintype "passive"))
      (node (ref "U27") (pin "7") (pinfunction "~{STBY}_7") (pintype "passive"))
    )
    (net (code "116") (name "Net-(U28-INA)") (class "Default")
      (node (ref "R23") (pin "1") (pinfunction "1_1") (pintype "passive"))
      (node (ref "U28") (pin "2") (pinfunction "INA_2") (pintype "passive"))
    )
    (net (code "117") (name "Net-(U28-INB)") (class "Default")
      (node (ref "R117") (pin "1") (pinfunction "1_1") (pintype "passive"))
      (node (ref "U28") (pin "3") (pinfunction "INB_3") (pintype "passive"))
    )
    (net (code "118") (name "Net-(U28-INC)") (class "Default")
      (node (ref "R163") (pin "1") (pinfunction "1_1") (pintype "passive"))
      (node (ref "U28") (pin "4") (pinfunction "INC_4") (pintype "passive"))
    )
    (net (code "119") (name "Net-(U28-IND)") (class "Default")
      (node (ref "R165") (pin "1") (pinfunction "1_1") (pintype "passive"))
      (node (ref "U28") (pin "5") (pinfunction "IND_5") (pintype "passive"))
    )
    (net (code "120") (name "Net-(U28-INE)") (class "Default")
      (node (ref "R168") (pin "2") (pinfunction "2_2") (pintype "passive"))
      (node (ref "U28") (pin "11") (pinfunction "INE_11") (pintype "passive"))
    )
    (net (code "121") (name "Net-(U28-OUTA)") (class "Default")
      (node (ref "R112") (pin "2") (pinfunction "2_2") (pintype "passive"))
      (node (ref "U28") (pin "15") (pinfunction "OUTA_15") (pintype "passive"))
    )
    (net (code "122") (name "Net-(U28-OUTB)") (class "Default")
      (node (ref "R130") (pin "2") (pinfunction "2_2") (pintype "passive"))
      (node (ref "U28") (pin "14") (pinfunction "OUTB_14") (pintype "passive"))
    )
    (net (code "123") (name "Net-(U28-OUTC)") (class "Default")
      (node (ref "R164") (pin "2") (pinfunction "2_2") (pintype "passive"))
      (node (ref "U28") (pin "13") (pinfunction "OUTC_13") (pintype "passive"))
    )
    (net (code "124") (name "Net-(U28-OUTD)") (class "Default")
      (node (ref "R166") (pin "2") (pinfunction "2_2") (pintype "passive"))
      (node (ref "U28") (pin "12") (pinfunction "OUTD_12") (pintype "passive"))
    )
    (net (code "125") (name "Net-(U28-OUTE)") (class "Default")
      (node (ref "R167") (pin "1") (pinfunction "1_1") (pintype "passive"))
      (node (ref "U28") (pin "6") (pinfunction "OUTE_6") (pintype "passive"))
    )
    (net (code "126") (name "Net-(U30-GAIN)") (class "Default")
      (node (ref "R150") (pin "2") (pinfunction "2_2") (pintype "passive"))
      (node (ref "U30") (pin "10") (pinfunction "GAIN_10") (pintype "passive"))
    )
    (net (code "127") (name "unconnected-(A1-Pad2)") (class "Default")
      (node (ref "A1") (pin "2") (pinfunction "2_2") (pintype "passive"))
    )
    (net (code "128") (name "unconnected-(A4-Pad1)") (class "Default")
      (node (ref "A4") (pin "1") (pinfunction "1_1") (pintype "passive"))
    )
    (net (code "129") (name "unconnected-(U22-RCOUT-Pad7)") (class "Default")
      (node (ref "U22") (pin "7") (pinfunction "RCOUT_7") (pintype "passive"))
    )
    (net (code "130") (name "unconnected-(U27-FRSTDATA-Pad15)") (class "Default")
      (node (ref "U27") (pin "15") (pinfunction "FRSTDATA_15") (pintype "passive"))
    )
    (net (code "131") (name "unconnected-(U28-NC-Pad7)") (class "Default")
      (node (ref "U28") (pin "7") (pinfunction "NC_7") (pintype "passive"))
    )
    (net (code "132") (name "unconnected-(U28-NC-Pad10)") (class "Default")
      (node (ref "U28") (pin "10") (pinfunction "NC_10") (pintype "passive"))
    )
    (net (code "133") (name "unconnected-(U29-DNC-Pad1)") (class "Default")
      (node (ref "U29") (pin "1") (pinfunction "DNC_1") (pintype "passive"))
    )
    (net (code "134") (name "unconnected-(U29-DNC-Pad8)") (class "Default")
      (node (ref "U29") (pin "8") (pinfunction "DNC_8") (pintype "passive"))
    )
    (net (code "135") (name "unconnected-(U29-NC-Pad7)") (class "Default")
      (node (ref "U29") (pin "7") (pinfunction "NC_7") (pintype "passive"))
    )
    (net (code "136") (name "unconnected-(U29-TEMP-Pad3)") (class "Default")
      (node (ref "U29") (pin "3") (pinfunction "TEMP_3") (pintype "passive"))
    )
    (net (code "137") (name "unconnected-(U29-TRIM{slash}NR-Pad5)") (class "Default")
      (node (ref "U29") (pin "5") (pinfunction "TRIM/NR_5") (pintype "passive"))
    )
    (net (code "138") (name "unconnected-(U30-RESET-Pad15)") (class "Default")
      (node (ref "U30") (pin "15") (pinfunction "RESET_15") (pintype "passive"))
    )
    (net (code "139") (name "unconnected-(U30-SOD-Pad8)") (class "Default")
      (node (ref "U30") (pin "8") (pinfunction "SOD_8") (pintype "passive"))
    )
  )
)
